# mk312_smt_main_V2a.net
KiCad netlist of a schematic drawn in EAGLE
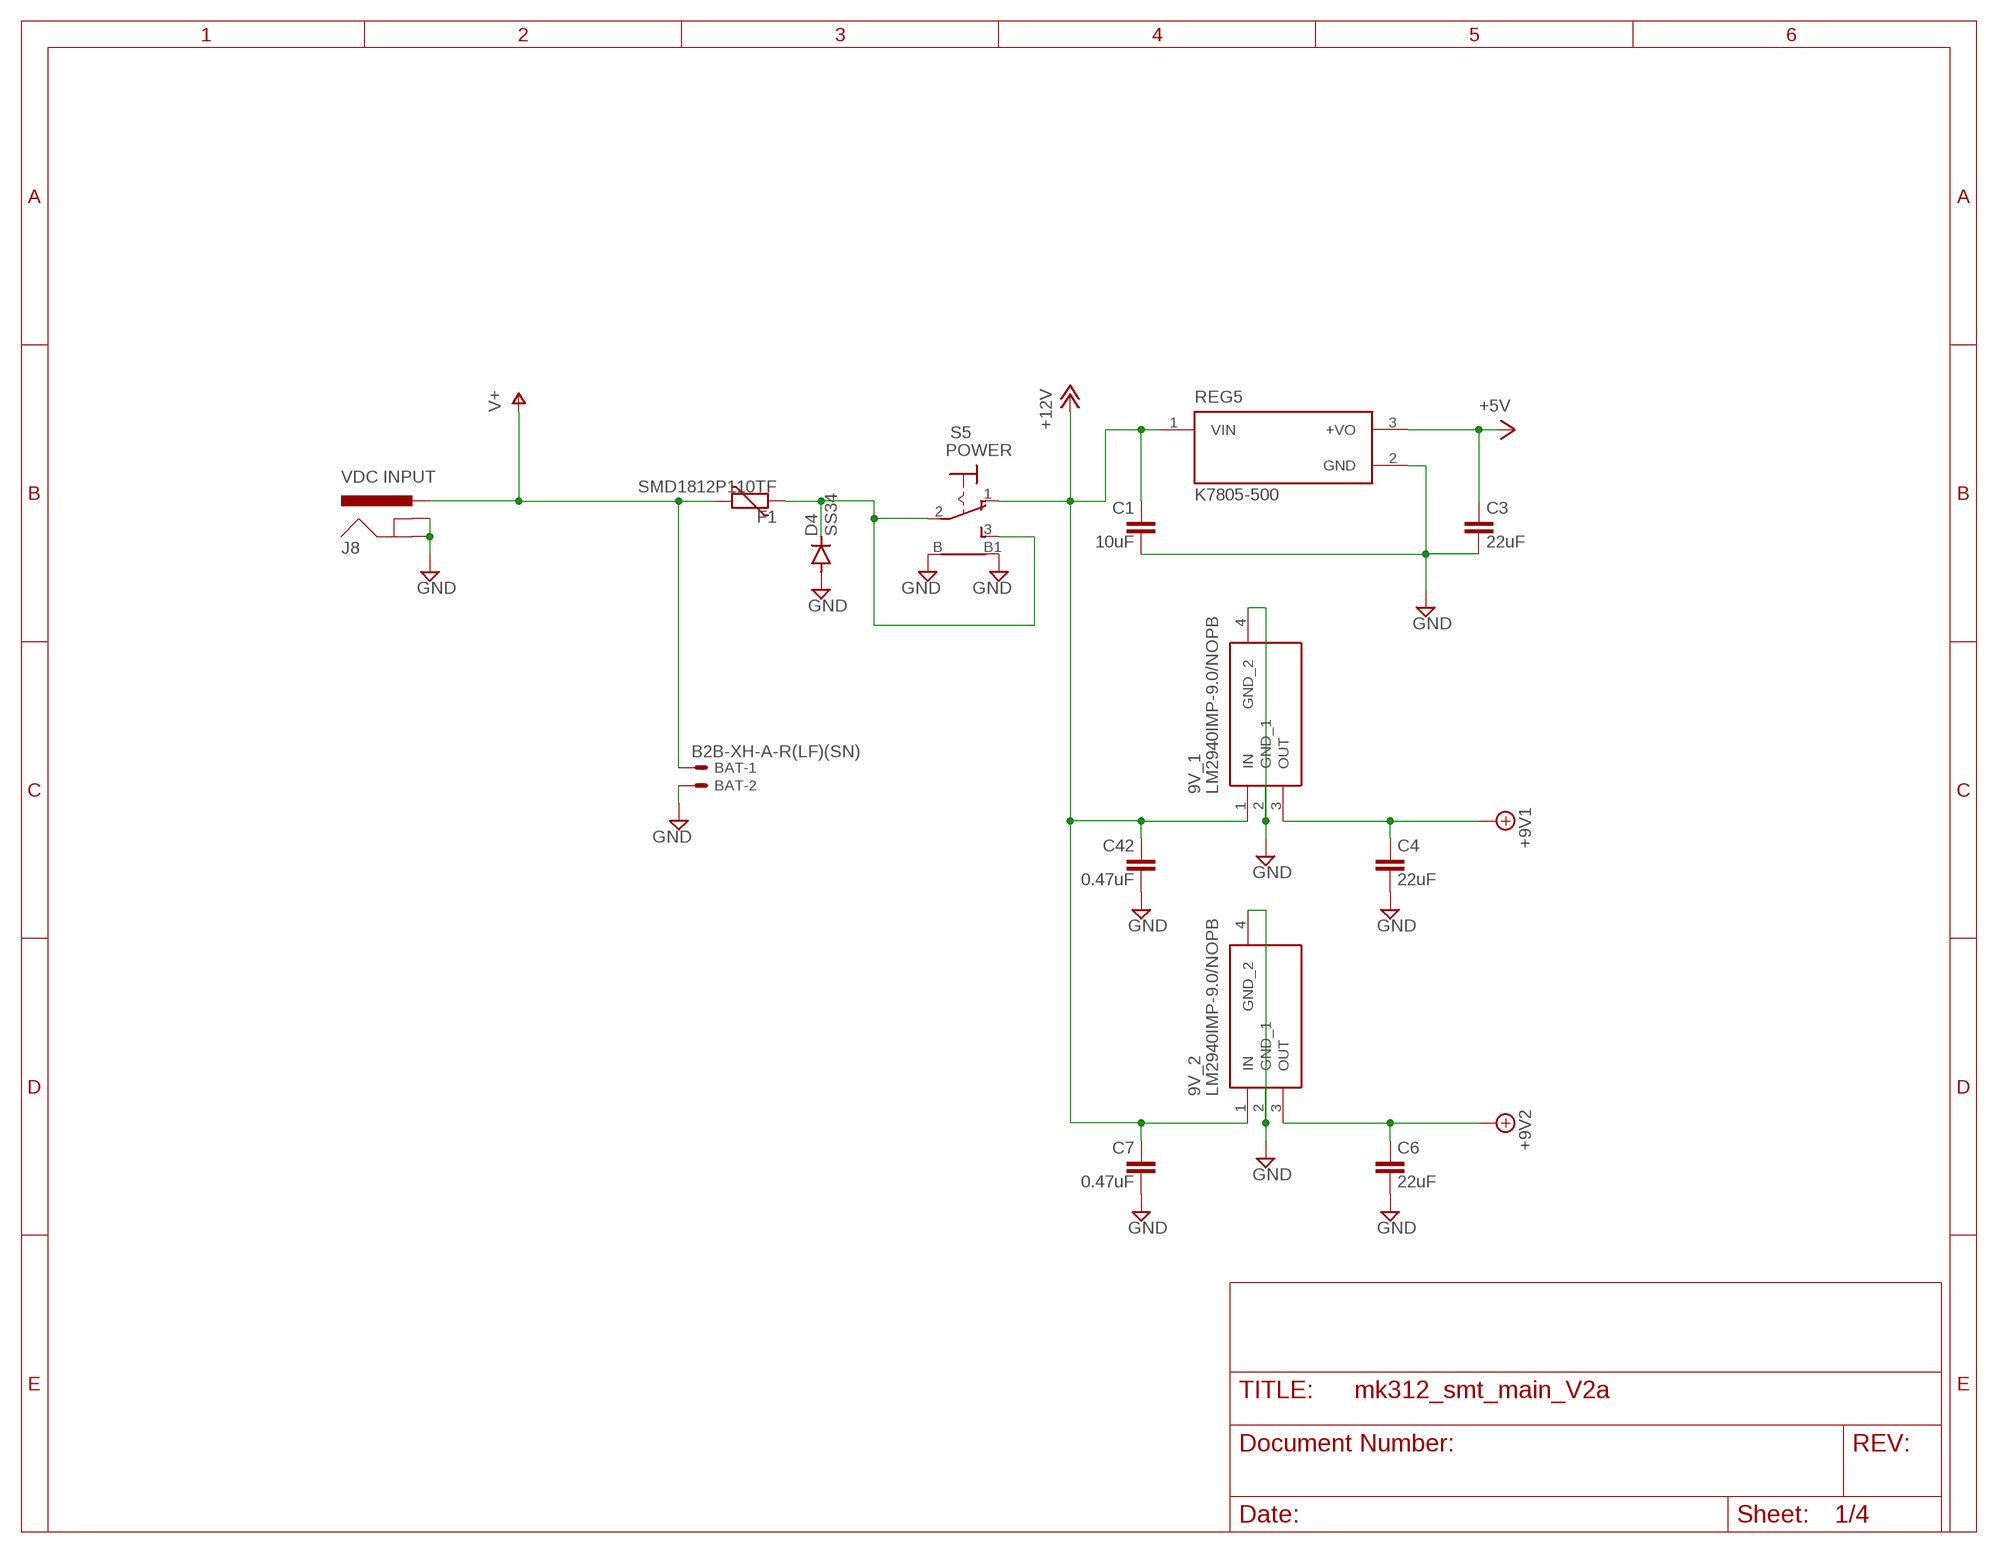
[diagram p0: schematic, sheet 1]
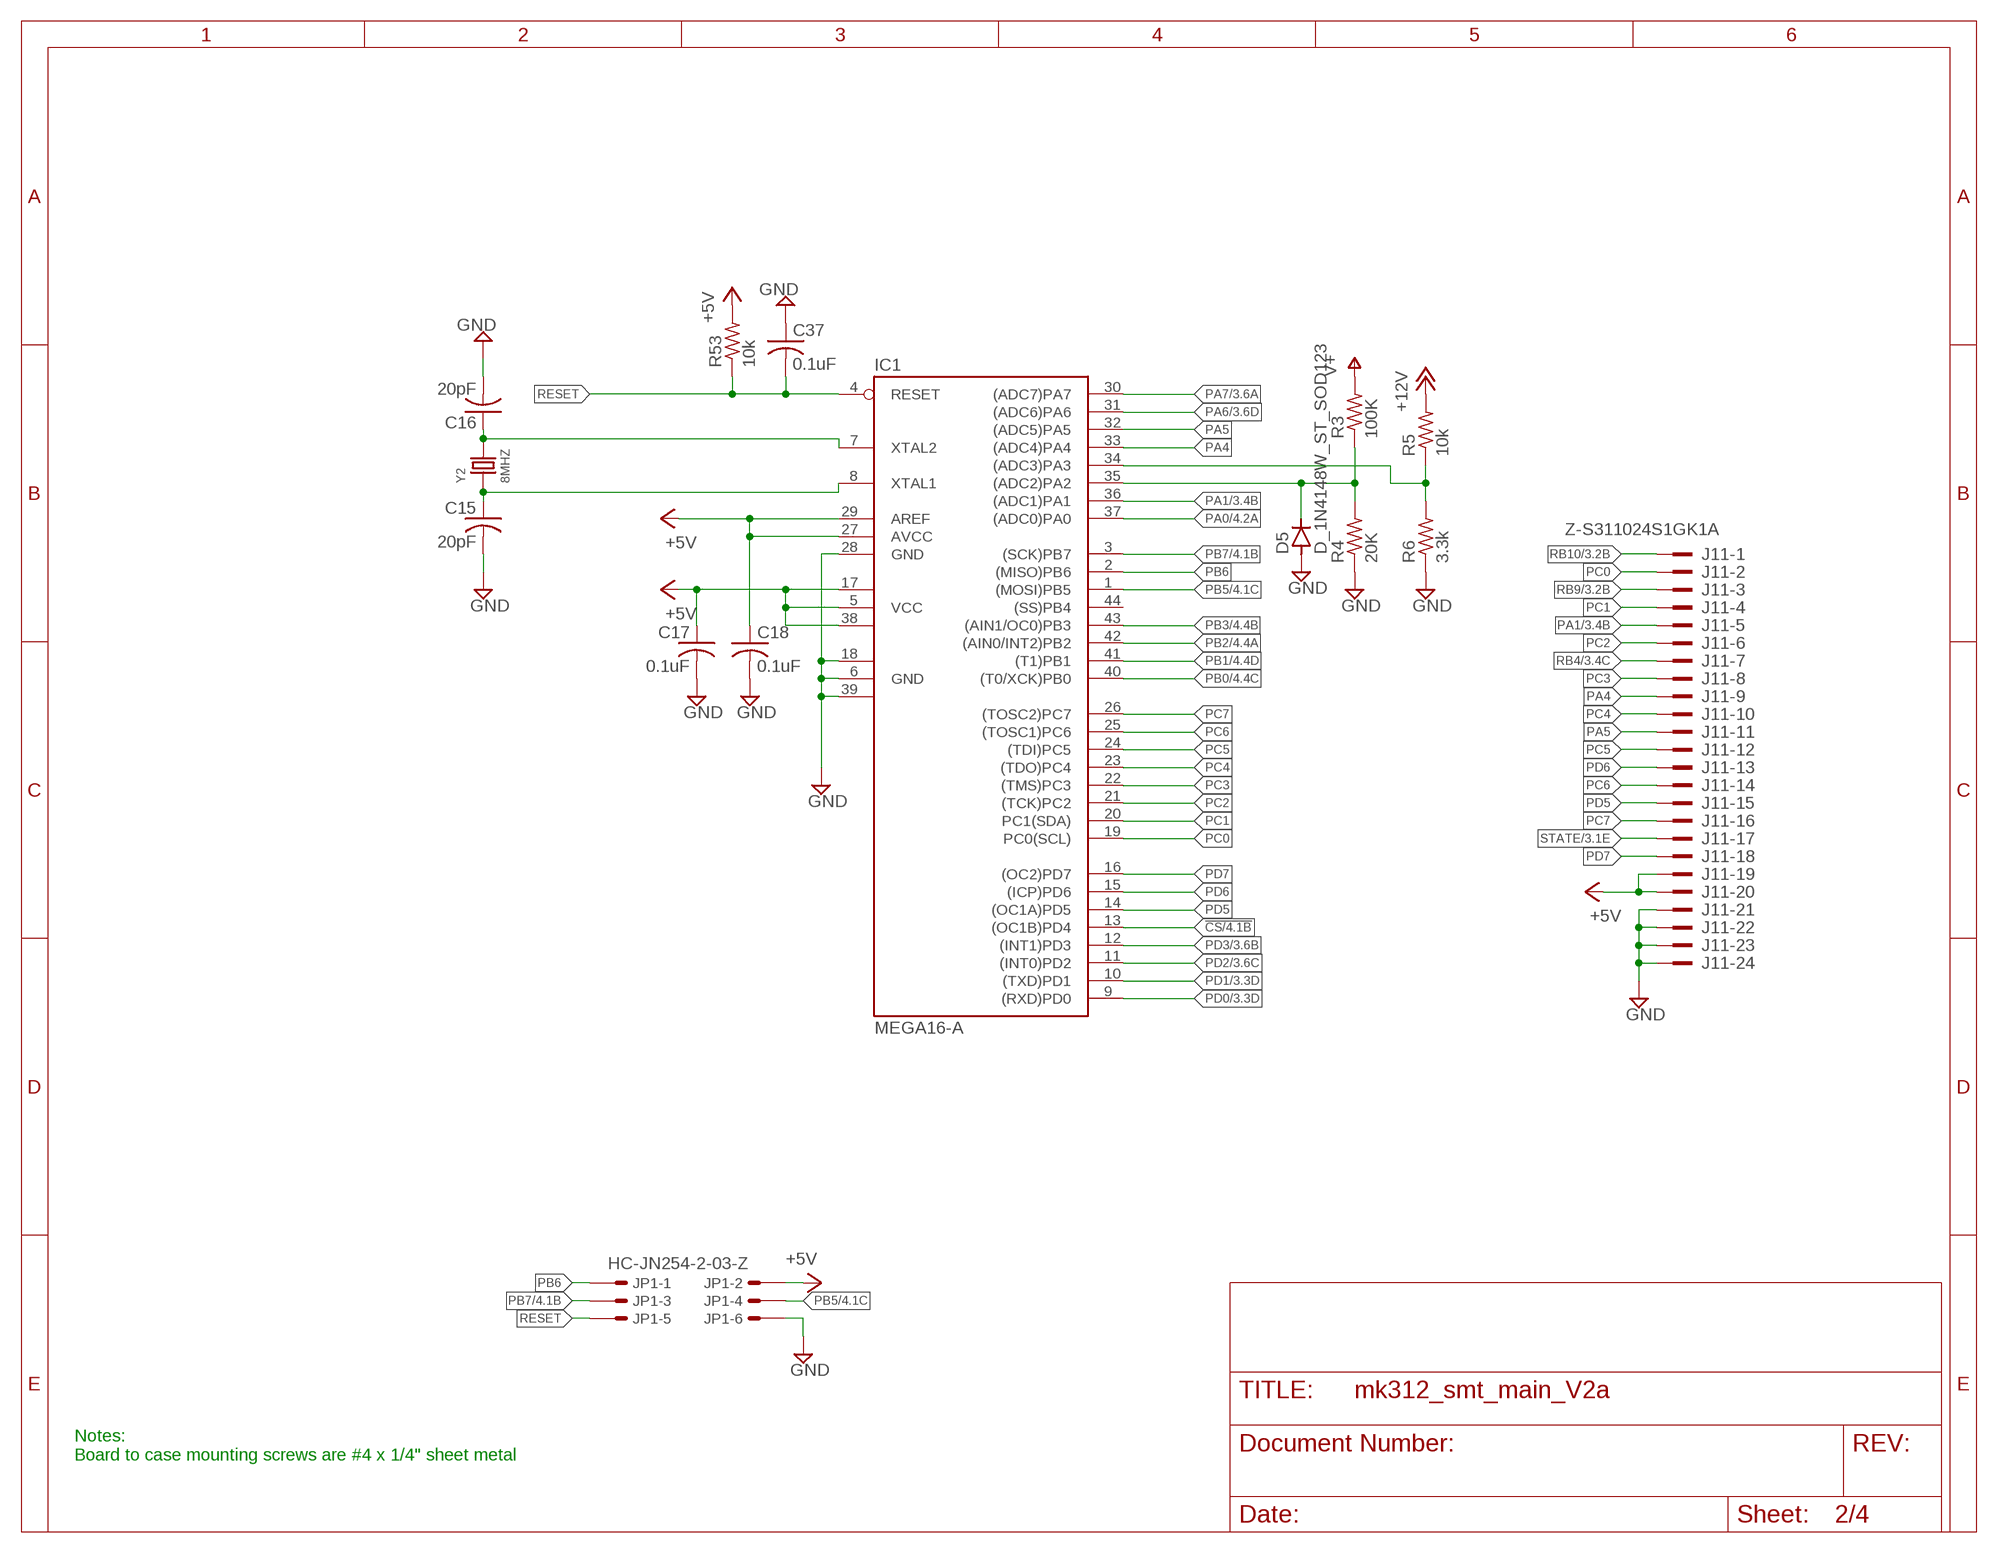
[diagram p1: schematic, sheet 2]
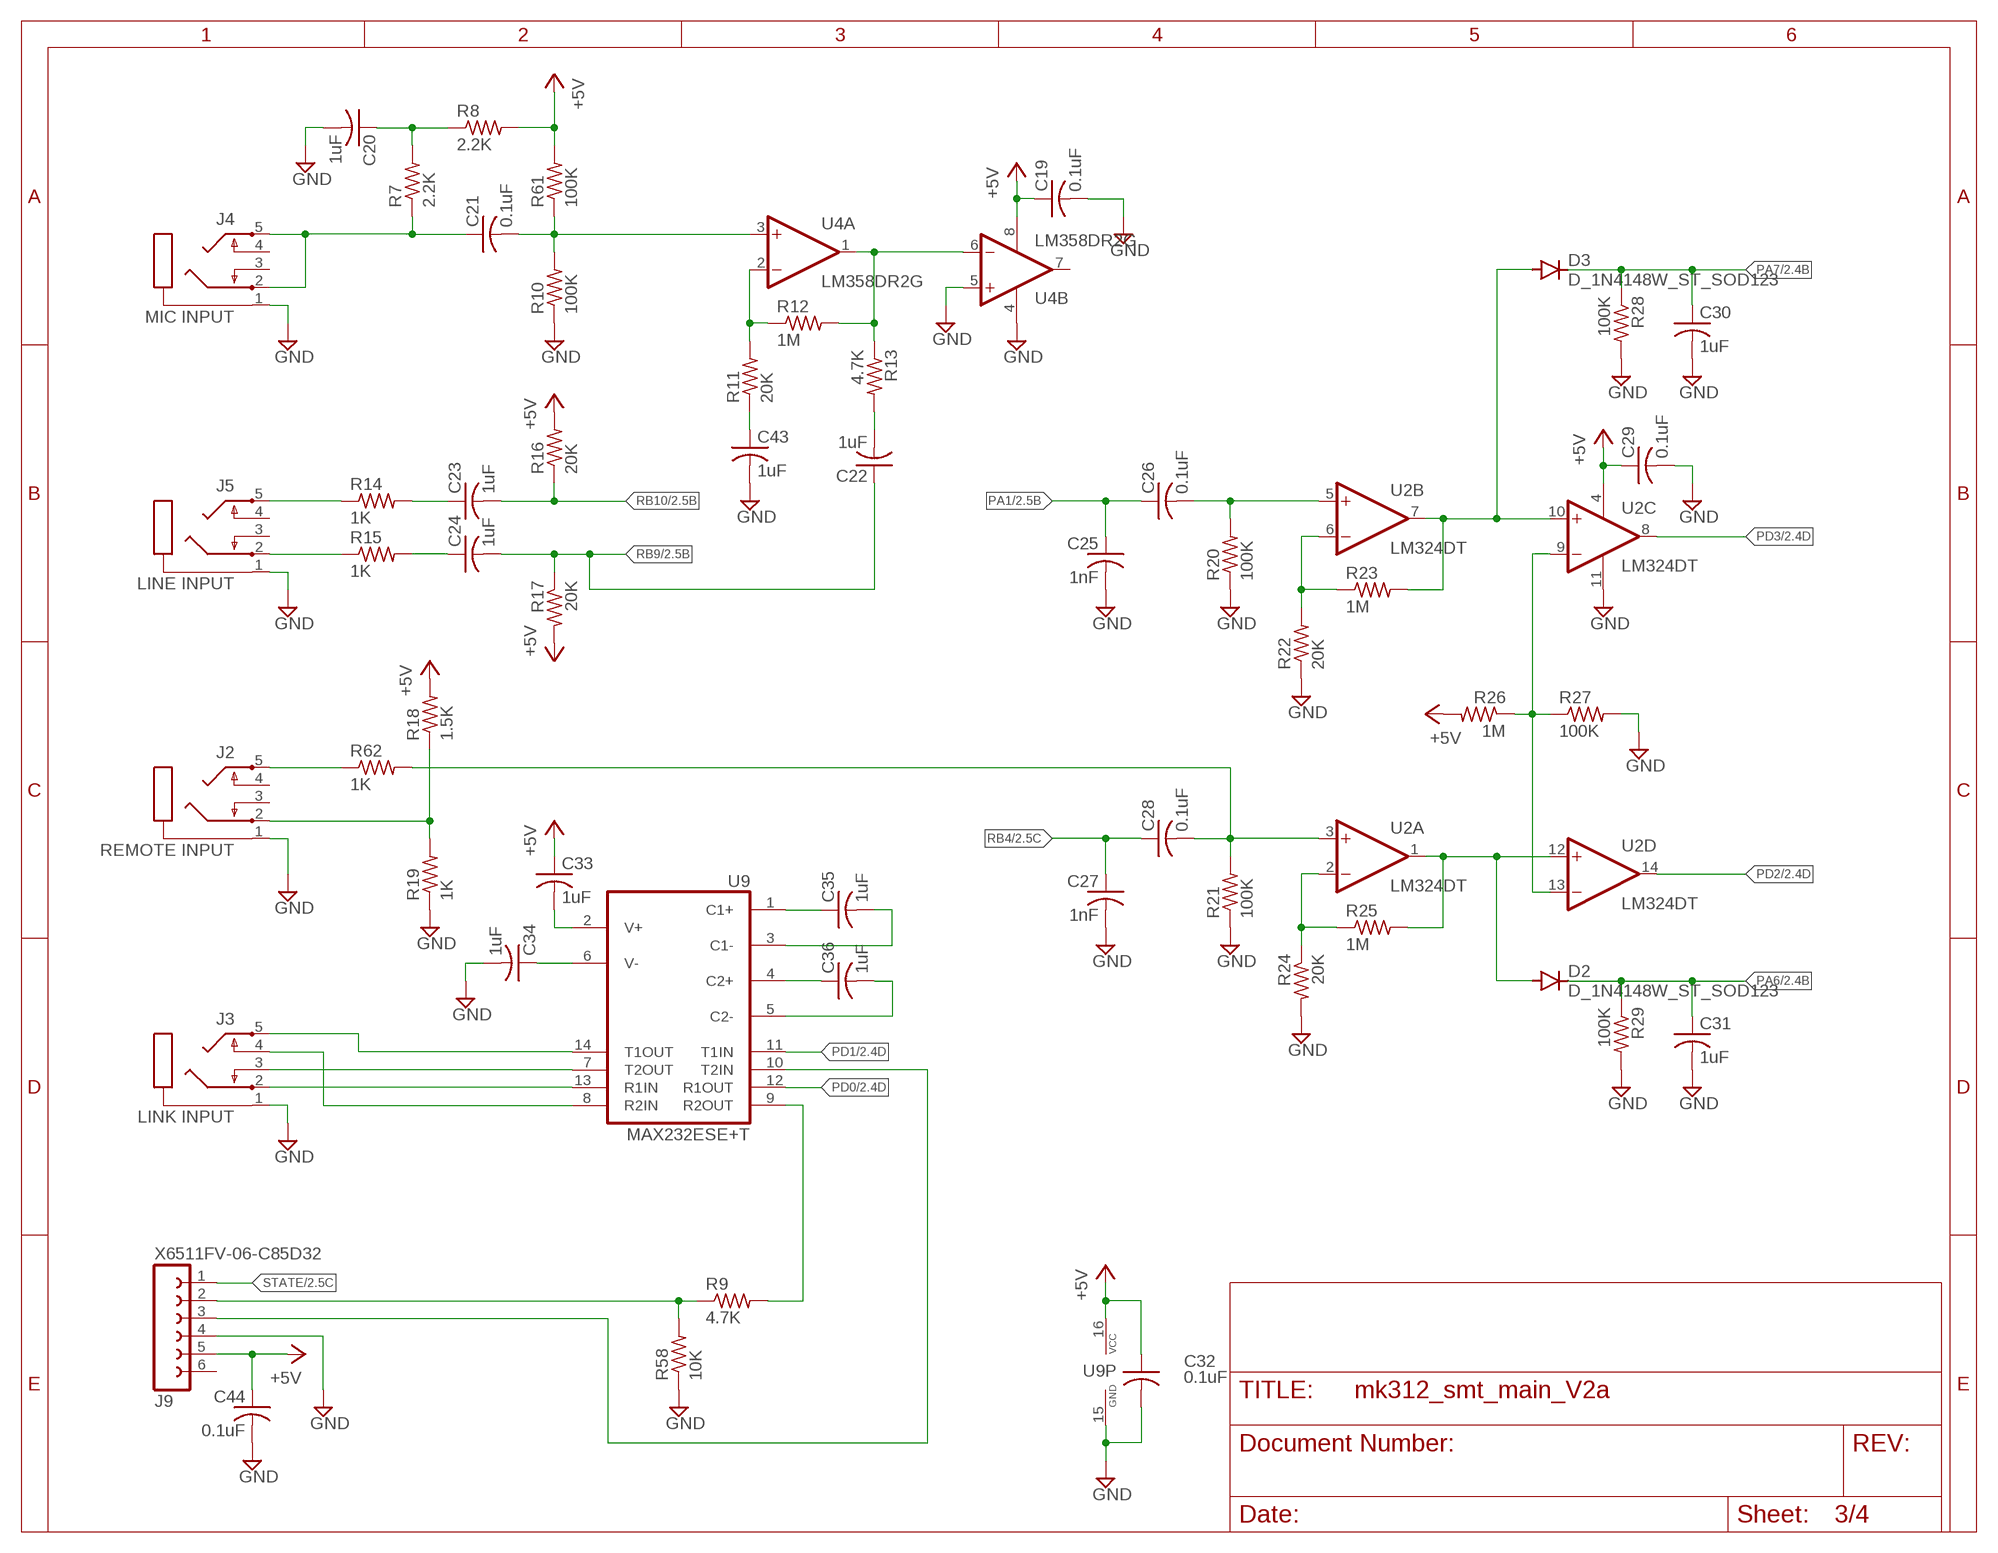
[diagram p2: schematic, sheet 3]
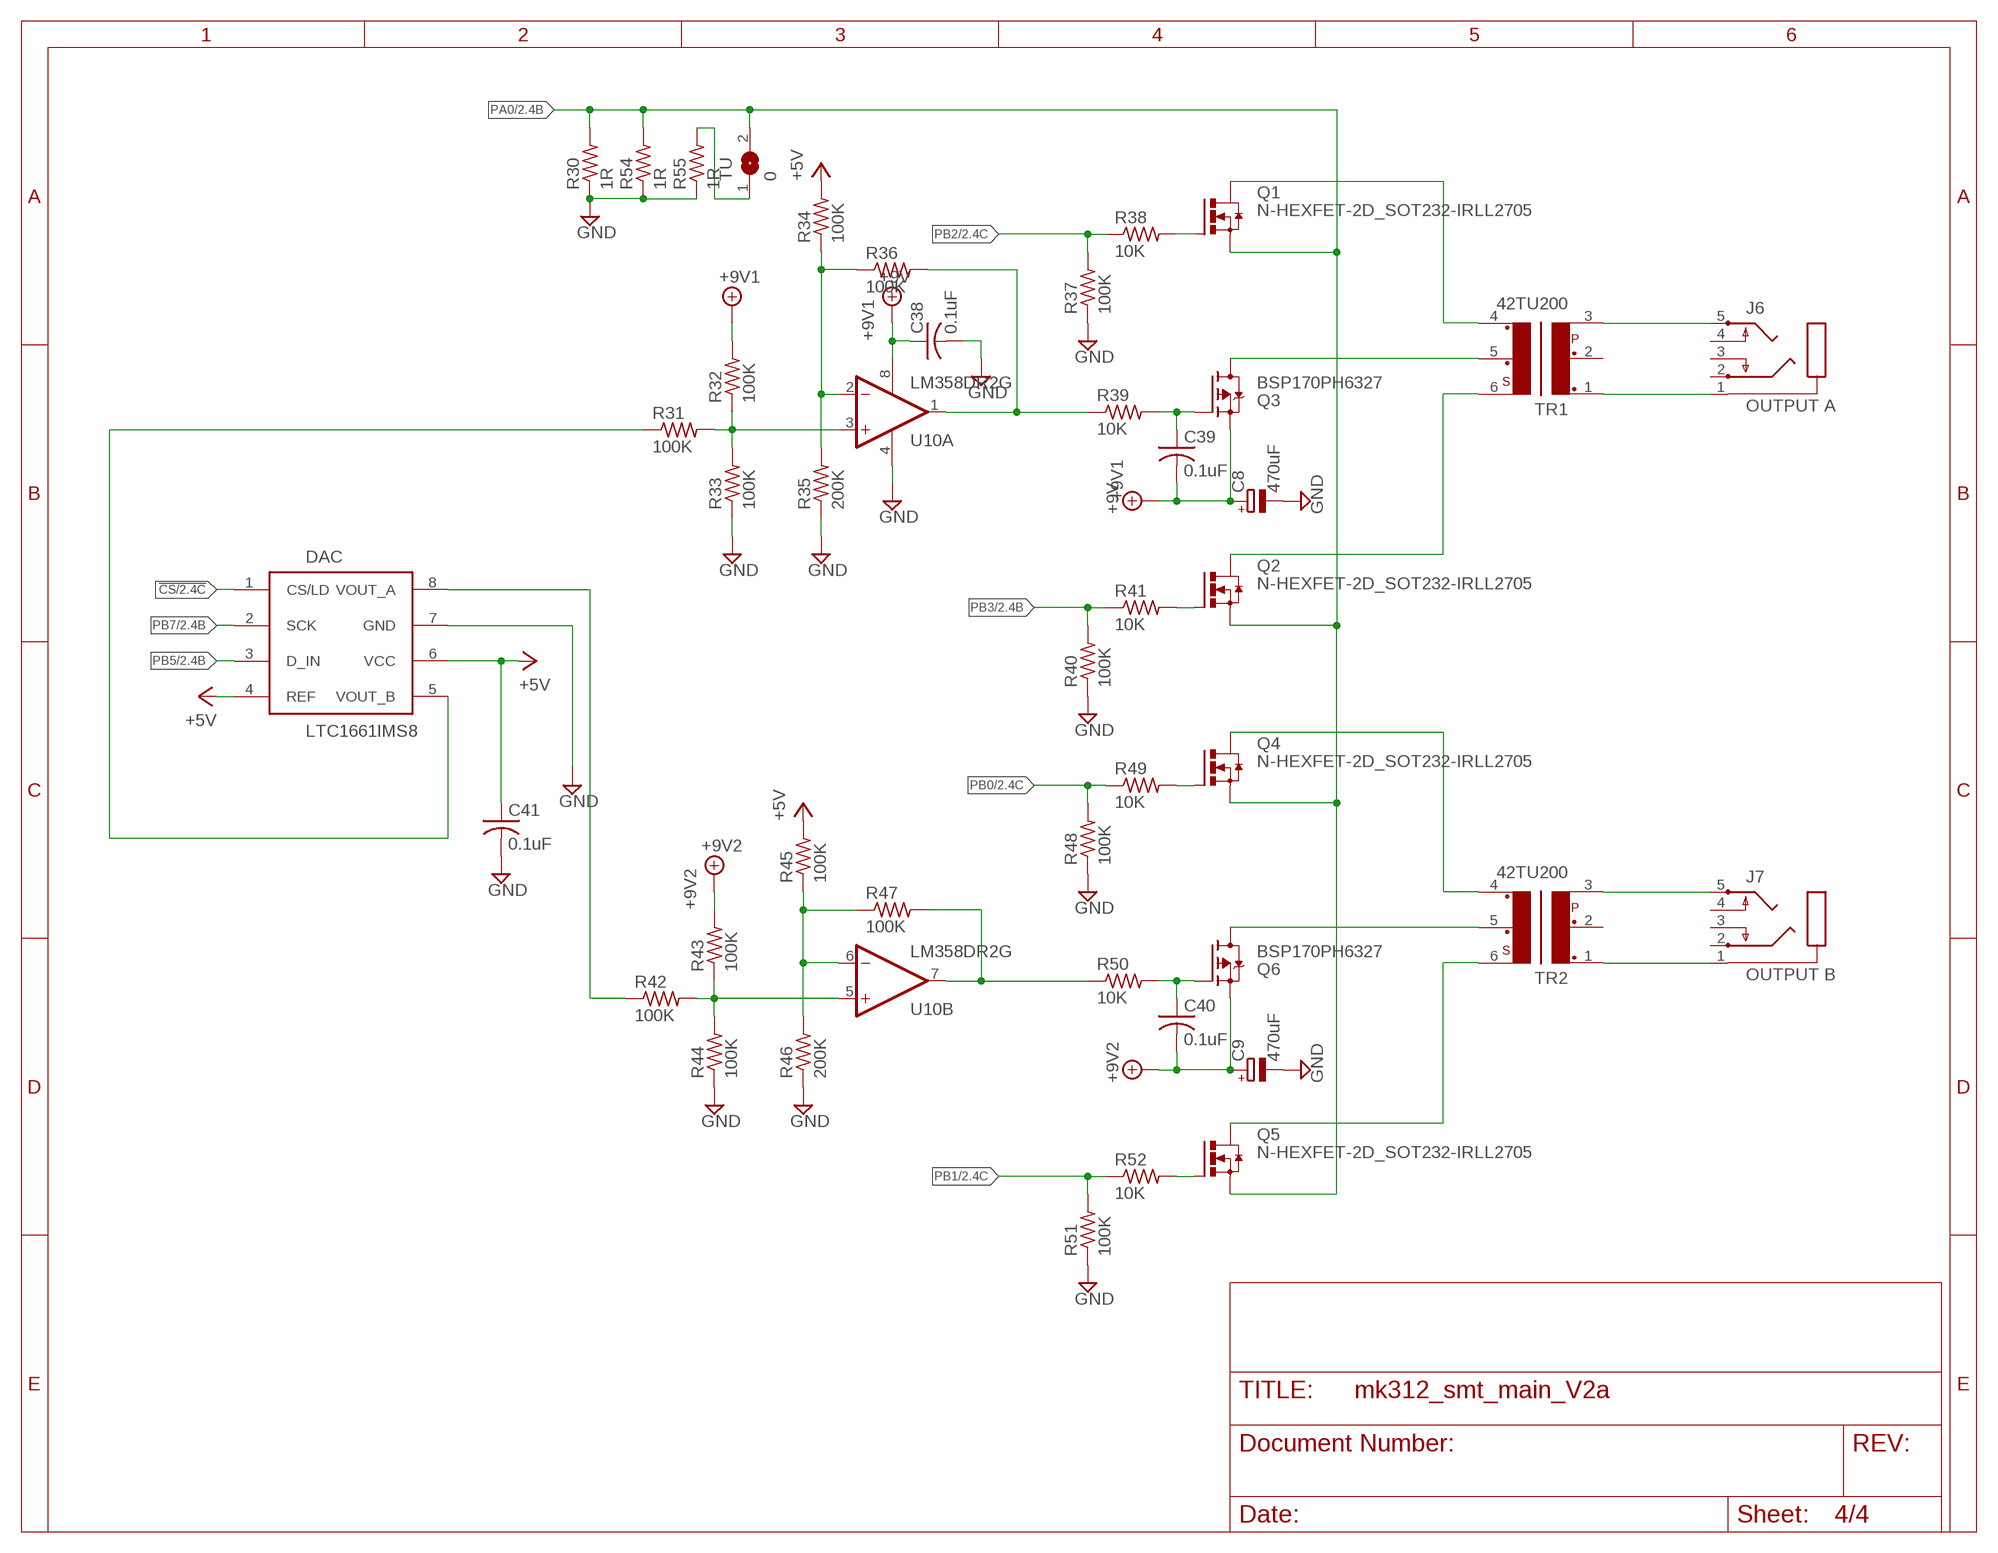
[diagram p3: schematic, sheet 4]

(export (version "E")
  (design (tool "Eeschema 10.0.6"))
  (components
    (comp (ref "C15")
      (value "20pF")
      (footprint "eagle-import:C0603")
      (libsource (lib "eagle-import") (part "C-USC0603"))
    )
    (comp (ref "C16")
      (value "20pF")
      (footprint "eagle-import:C0603")
      (libsource (lib "eagle-import") (part "C-USC0603"))
    )
    (comp (ref "C17")
      (value "0.1uF")
      (footprint "eagle-import:C0805")
      (libsource (lib "eagle-import") (part "C-USC0805"))
    )
    (comp (ref "C18")
      (value "0.1uF")
      (footprint "eagle-import:C0805")
      (libsource (lib "eagle-import") (part "C-USC0805"))
    )
    (comp (ref "C37")
      (value "0.1uF")
      (footprint "eagle-import:C0805")
      (libsource (lib "eagle-import") (part "rcl_334_C-USC0805"))
    )
    (comp (ref "D5")
      (value "D_1N4148W_ST_SOD123")
      (footprint "eagle-import:SOD123")
      (fields (field (name "LCSC_PART") "C81598"))
      (libsource (lib "eagle-import") (part "D__SOD1231N4148W_ST"))
    )
    (comp (ref "IC1")
      (value "MEGA16-A")
      (footprint "eagle-import:TQFP44")
      (fields (field (name "MPN") "ATMEGA16-16AU"))
      (libsource (lib "eagle-import") (part "MEGA16-A"))
    )
    (comp (ref "J11")
      (value "Z-S311024S1GK1A")
      (footprint "eagle-import:PAK100_2500-24")
      (libsource (lib "eagle-import") (part "2524-"))
    )
    (comp (ref "JP1")
      (value "HC-JN254-2-03-Z")
      (footprint "eagle-import:057-006-1")
      (libsource (lib "eagle-import") (part "057-006-1"))
    )
    (comp (ref "R3")
      (value "100K")
      (footprint "eagle-import:R0805")
      (libsource (lib "eagle-import") (part "R-US_R0805"))
    )
    (comp (ref "R4")
      (value "20K")
      (footprint "eagle-import:R0805")
      (libsource (lib "eagle-import") (part "R-US_R0805"))
    )
    (comp (ref "R5")
      (value "10k")
      (footprint "eagle-import:R0805")
      (libsource (lib "eagle-import") (part "R-US_R0805"))
    )
    (comp (ref "R6")
      (value "3.3k")
      (footprint "eagle-import:R0805")
      (libsource (lib "eagle-import") (part "R-US_R0805"))
    )
    (comp (ref "R53")
      (value "10k")
      (footprint "eagle-import:R0805")
      (libsource (lib "eagle-import") (part "rcl_334_R-US_R0805"))
    )
    (comp (ref "Y2")
      (value "8MHZ")
      (footprint "eagle-import:X2-SMD-5.0X3.2X1.3MM")
      (fields (field (name "MPN") "5032/2P"))
      (libsource (lib "eagle-import") (part "SMD-CRYSTAL-8MHZ-20PF-20PPM(2P-5.0X3.2MM)"))
    )
    (comp (ref "C8")
      (value "470uF")
      (footprint "eagle-import:150CLZ-1010")
      (libsource (lib "eagle-import") (part "CPOL-EU150CLZ-1010"))
    )
    (comp (ref "C9")
      (value "470uF")
      (footprint "eagle-import:150CLZ-1010")
      (libsource (lib "eagle-import") (part "CPOL-EU150CLZ-1010"))
    )
    (comp (ref "C38")
      (value "0.1uF")
      (footprint "eagle-import:C0805")
      (libsource (lib "eagle-import") (part "C-USC0805"))
    )
    (comp (ref "C39")
      (value "0.1uF")
      (footprint "eagle-import:C0805")
      (libsource (lib "eagle-import") (part "C-USC0805"))
    )
    (comp (ref "C40")
      (value "0.1uF")
      (footprint "eagle-import:C0805")
      (libsource (lib "eagle-import") (part "C-USC0805"))
    )
    (comp (ref "C41")
      (value "0.1uF")
      (footprint "eagle-import:C0805")
      (libsource (lib "eagle-import") (part "C-USC0805"))
    )
    (comp (ref "DAC")
      (value "LTC1661IMS8")
      (footprint "eagle-import:MSOP8")
      (libsource (lib "eagle-import") (part "LTC1661IMS8"))
    )
    (comp (ref "J6")
      (value "OUTPUT A")
      (footprint "eagle-import:PJ-3062")
      (libsource (lib "eagle-import") (part "STEREOJACKPJ-3062"))
    )
    (comp (ref "J7")
      (value "OUTPUT B")
      (footprint "eagle-import:PJ-3062")
      (libsource (lib "eagle-import") (part "STEREOJACKPJ-3062"))
    )
    (comp (ref "Q1")
      (value "N-HEXFET-2D_SOT232-IRLL2705")
      (footprint "eagle-import:SOT223")
      (libsource (lib "eagle-import") (part "N-HEXFET-2D_?-SOT232IRLL2705"))
    )
    (comp (ref "Q2")
      (value "N-HEXFET-2D_SOT232-IRLL2705")
      (footprint "eagle-import:SOT223")
      (libsource (lib "eagle-import") (part "N-HEXFET-2D_?-SOT232IRLL2705"))
    )
    (comp (ref "Q3")
      (value "BSP170PH6327")
      (footprint "eagle-import:SOT230P700X180-4N")
      (libsource (lib "eagle-import") (part "IRFL9014TRPBF"))
    )
    (comp (ref "Q4")
      (value "N-HEXFET-2D_SOT232-IRLL2705")
      (footprint "eagle-import:SOT223")
      (libsource (lib "eagle-import") (part "N-HEXFET-2D_?-SOT232IRLL2705"))
    )
    (comp (ref "Q5")
      (value "N-HEXFET-2D_SOT232-IRLL2705")
      (footprint "eagle-import:SOT223")
      (libsource (lib "eagle-import") (part "N-HEXFET-2D_?-SOT232IRLL2705"))
    )
    (comp (ref "Q6")
      (value "BSP170PH6327")
      (footprint "eagle-import:SOT230P700X180-4N")
      (libsource (lib "eagle-import") (part "IRFL9014TRPBF"))
    )
    (comp (ref "R30")
      (value "1R")
      (footprint "eagle-import:R1206")
      (libsource (lib "eagle-import") (part "R-US_R1206"))
    )
    (comp (ref "R31")
      (value "100K")
      (footprint "eagle-import:R0805")
      (libsource (lib "eagle-import") (part "R-US_R0805"))
    )
    (comp (ref "R32")
      (value "100K")
      (footprint "eagle-import:R0805")
      (libsource (lib "eagle-import") (part "R-US_R0805"))
    )
    (comp (ref "R33")
      (value "100K")
      (footprint "eagle-import:R0805")
      (libsource (lib "eagle-import") (part "R-US_R0805"))
    )
    (comp (ref "R34")
      (value "100K")
      (footprint "eagle-import:R0805")
      (libsource (lib "eagle-import") (part "R-US_R0805"))
    )
    (comp (ref "R35")
      (value "200K")
      (footprint "eagle-import:R0805")
      (libsource (lib "eagle-import") (part "R-US_R0805"))
    )
    (comp (ref "R36")
      (value "100K")
      (footprint "eagle-import:R0805")
      (libsource (lib "eagle-import") (part "R-US_R0805"))
    )
    (comp (ref "R37")
      (value "100K")
      (footprint "eagle-import:R0805")
      (libsource (lib "eagle-import") (part "R-US_R0805"))
    )
    (comp (ref "R38")
      (value "10K")
      (footprint "eagle-import:R0805")
      (libsource (lib "eagle-import") (part "R-US_R0805"))
    )
    (comp (ref "R39")
      (value "10K")
      (footprint "eagle-import:R0805")
      (libsource (lib "eagle-import") (part "R-US_R0805"))
    )
    (comp (ref "R40")
      (value "100K")
      (footprint "eagle-import:R0805")
      (libsource (lib "eagle-import") (part "R-US_R0805"))
    )
    (comp (ref "R41")
      (value "10K")
      (footprint "eagle-import:R0805")
      (libsource (lib "eagle-import") (part "R-US_R0805"))
    )
    (comp (ref "R42")
      (value "100K")
      (footprint "eagle-import:R0805")
      (libsource (lib "eagle-import") (part "R-US_R0805"))
    )
    (comp (ref "R43")
      (value "100K")
      (footprint "eagle-import:R0805")
      (libsource (lib "eagle-import") (part "R-US_R0805"))
    )
    (comp (ref "R44")
      (value "100K")
      (footprint "eagle-import:R0805")
      (libsource (lib "eagle-import") (part "R-US_R0805"))
    )
    (comp (ref "R45")
      (value "100K")
      (footprint "eagle-import:R0805")
      (libsource (lib "eagle-import") (part "R-US_R0805"))
    )
    (comp (ref "R46")
      (value "200K")
      (footprint "eagle-import:R0805")
      (libsource (lib "eagle-import") (part "R-US_R0805"))
    )
    (comp (ref "R47")
      (value "100K")
      (footprint "eagle-import:R0805")
      (libsource (lib "eagle-import") (part "R-US_R0805"))
    )
    (comp (ref "R48")
      (value "100K")
      (footprint "eagle-import:R0805")
      (libsource (lib "eagle-import") (part "R-US_R0805"))
    )
    (comp (ref "R49")
      (value "10K")
      (footprint "eagle-import:R0805")
      (libsource (lib "eagle-import") (part "R-US_R0805"))
    )
    (comp (ref "R50")
      (value "10K")
      (footprint "eagle-import:R0805")
      (libsource (lib "eagle-import") (part "R-US_R0805"))
    )
    (comp (ref "R51")
      (value "100K")
      (footprint "eagle-import:R0805")
      (libsource (lib "eagle-import") (part "R-US_R0805"))
    )
    (comp (ref "R52")
      (value "10K")
      (footprint "eagle-import:R0805")
      (libsource (lib "eagle-import") (part "R-US_R0805"))
    )
    (comp (ref "R54")
      (value "1R")
      (footprint "eagle-import:R1206")
      (libsource (lib "eagle-import") (part "R-US_R1206"))
    )
    (comp (ref "R55")
      (value "1R")
      (footprint "eagle-import:R1206")
      (libsource (lib "eagle-import") (part "R-US_R1206"))
    )
    (comp (ref "TR1")
      (value "42TU200")
      (footprint "eagle-import:42TL")
      (libsource (lib "eagle-import") (part "42T?42TU"))
    )
    (comp (ref "TR2")
      (value "42TU200")
      (footprint "eagle-import:42TL")
      (libsource (lib "eagle-import") (part "42T?42TU"))
    )
    (comp (ref "TU") (value "0") (footprint "eagle-import:SJ") (libsource (lib "eagle-import") (part "SJ")))
    (comp (ref "U10")
      (value "LM358DR2G")
      (footprint "eagle-import:SO08")
      (libsource (lib "eagle-import") (part "LM358D"))
    )
    (comp (ref "9V_1")
      (value "LM2940IMP-9.0/NOPB")
      (footprint "eagle-import:SOT230P700X180-4N")
      (fields (field (name "MOUSER_PART_NUMBER") "926-LM2940IMP90NOPB"))
      (libsource (lib "eagle-import") (part "LM2940IMP-9.0_NOPB"))
    )
    (comp (ref "9V_2")
      (value "LM2940IMP-9.0/NOPB")
      (footprint "eagle-import:SOT230P700X180-4N")
      (fields (field (name "MOUSER_PART_NUMBER") "926-LM2940IMP90NOPB"))
      (libsource (lib "eagle-import") (part "LM2940IMP-9.0_NOPB"))
    )
    (comp (ref "BAT")
      (value "B2B-XH-A-R(LF)(SN)")
      (footprint "eagle-import:JST-XH-02-PACKAGE-LONG-PAD")
      (libsource (lib "eagle-import") (part "JST-XH-02-PIN-LONG-PAD"))
    )
    (comp (ref "C1")
      (value "10uF")
      (footprint "eagle-import:C0805")
      (libsource (lib "eagle-import") (part "C-EUC0805"))
    )
    (comp (ref "C3")
      (value "22uF")
      (footprint "eagle-import:C1206")
      (libsource (lib "eagle-import") (part "C-EUC1206"))
    )
    (comp (ref "C4")
      (value "22uF")
      (footprint "eagle-import:C1206")
      (libsource (lib "eagle-import") (part "C-EUC1206"))
    )
    (comp (ref "C6")
      (value "22uF")
      (footprint "eagle-import:C1206")
      (libsource (lib "eagle-import") (part "C-EUC1206"))
    )
    (comp (ref "C7")
      (value "0.47uF")
      (footprint "eagle-import:C0805")
      (libsource (lib "eagle-import") (part "C-EUC0805"))
    )
    (comp (ref "C42")
      (value "0.47uF")
      (footprint "eagle-import:C0805")
      (libsource (lib "eagle-import") (part "C-EUC0805"))
    )
    (comp (ref "D4")
      (value "SS34")
      (footprint "eagle-import:SMA")
      (libsource (lib "eagle-import") (part "S1M"))
    )
    (comp (ref "F1")
      (value "SMD1812P110TF")
      (footprint "eagle-import:CT_CN1812")
      (libsource (lib "eagle-import") (part "VARISTORCN1812"))
    )
    (comp (ref "J8")
      (value "VDC INPUT")
      (footprint "eagle-import:POWER_JACK_PTH_SLOT")
      (libsource (lib "eagle-import") (part "POWER_JACKPOWER_JACK_SLOT"))
    )
    (comp (ref "REG5")
      (value "K7805-500")
      (footprint "eagle-import:CONV_K7809M-1000R3")
      (fields (field (name "MF") "Mornsun America, LLC") (field (name "MP") "K7809M-1000R3"))
      (libsource (lib "eagle-import") (part "K7809M-1000R3"))
    )
    (comp (ref "S5")
      (value "POWER")
      (footprint "eagle-import:LPV-1")
      (libsource (lib "eagle-import") (part "LPV-1"))
    )
    (comp (ref "C19")
      (value "0.1uF")
      (footprint "eagle-import:C0805")
      (libsource (lib "eagle-import") (part "C-USC0805"))
    )
    (comp (ref "C20")
      (value "1uF")
      (footprint "eagle-import:C0805")
      (libsource (lib "eagle-import") (part "C-USC0805"))
    )
    (comp (ref "C21")
      (value "0.1uF")
      (footprint "eagle-import:C0805")
      (libsource (lib "eagle-import") (part "C-USC0805"))
    )
    (comp (ref "C22")
      (value "1uF")
      (footprint "eagle-import:C0805")
      (libsource (lib "eagle-import") (part "C-USC0805"))
    )
    (comp (ref "C23")
      (value "1uF")
      (footprint "eagle-import:C0805")
      (libsource (lib "eagle-import") (part "C-USC0805"))
    )
    (comp (ref "C24")
      (value "1uF")
      (footprint "eagle-import:C0805")
      (libsource (lib "eagle-import") (part "C-USC0805"))
    )
    (comp (ref "C25")
      (value "1nF")
      (footprint "eagle-import:C0805")
      (libsource (lib "eagle-import") (part "C-USC0805"))
    )
    (comp (ref "C26")
      (value "0.1uF")
      (footprint "eagle-import:C0805")
      (libsource (lib "eagle-import") (part "C-USC0805"))
    )
    (comp (ref "C27")
      (value "1nF")
      (footprint "eagle-import:C0805")
      (libsource (lib "eagle-import") (part "C-USC0805"))
    )
    (comp (ref "C28")
      (value "0.1uF")
      (footprint "eagle-import:C0805")
      (libsource (lib "eagle-import") (part "C-USC0805"))
    )
    (comp (ref "C29")
      (value "0.1uF")
      (footprint "eagle-import:C0805")
      (libsource (lib "eagle-import") (part "C-USC0805"))
    )
    (comp (ref "C30")
      (value "1uF")
      (footprint "eagle-import:C0805")
      (libsource (lib "eagle-import") (part "C-USC0805"))
    )
    (comp (ref "C31")
      (value "1uF")
      (footprint "eagle-import:C0805")
      (libsource (lib "eagle-import") (part "C-USC0805"))
    )
    (comp (ref "C32")
      (value "0.1uF")
      (footprint "eagle-import:C0805")
      (libsource (lib "eagle-import") (part "C-USC0805"))
    )
    (comp (ref "C33")
      (value "1uF")
      (footprint "eagle-import:C0805")
      (libsource (lib "eagle-import") (part "C-USC0805"))
    )
    (comp (ref "C34")
      (value "1uF")
      (footprint "eagle-import:C0805")
      (libsource (lib "eagle-import") (part "C-USC0805"))
    )
    (comp (ref "C35")
      (value "1uF")
      (footprint "eagle-import:C0805")
      (libsource (lib "eagle-import") (part "C-USC0805"))
    )
    (comp (ref "C36")
      (value "1uF")
      (footprint "eagle-import:C0805")
      (libsource (lib "eagle-import") (part "C-USC0805"))
    )
    (comp (ref "C43")
      (value "1uF")
      (footprint "eagle-import:C0805")
      (libsource (lib "eagle-import") (part "C-USC0805"))
    )
    (comp (ref "C44")
      (value "0.1uF")
      (footprint "eagle-import:C0805")
      (libsource (lib "eagle-import") (part "C-USC0805"))
    )
    (comp (ref "D2")
      (value "D_1N4148W_ST_SOD123")
      (footprint "eagle-import:SOD123")
      (fields (field (name "LCSC_PART") "C81598"))
      (libsource (lib "eagle-import") (part "D__SOD1231N4148W_ST"))
    )
    (comp (ref "D3")
      (value "D_1N4148W_ST_SOD123")
      (footprint "eagle-import:SOD123")
      (fields (field (name "LCSC_PART") "C81598"))
      (libsource (lib "eagle-import") (part "D__SOD1231N4148W_ST"))
    )
    (comp (ref "J2")
      (value "REMOTE INPUT")
      (footprint "eagle-import:PJ-3062")
      (libsource (lib "eagle-import") (part "STEREOJACKPJ-3062"))
    )
    (comp (ref "J3")
      (value "LINK INPUT")
      (footprint "eagle-import:PJ-3062")
      (libsource (lib "eagle-import") (part "STEREOJACKPJ-3062"))
    )
    (comp (ref "J4")
      (value "MIC INPUT")
      (footprint "eagle-import:PJ-3062")
      (libsource (lib "eagle-import") (part "STEREOJACKPJ-3062"))
    )
    (comp (ref "J5")
      (value "LINE INPUT")
      (footprint "eagle-import:PJ-3062")
      (libsource (lib "eagle-import") (part "STEREOJACKPJ-3062"))
    )
    (comp (ref "J9")
      (value "X6511FV-06-C85D32")
      (footprint "eagle-import:FE06")
      (libsource (lib "eagle-import") (part "FE06-1"))
    )
    (comp (ref "R7")
      (value "2.2K")
      (footprint "eagle-import:R0805")
      (libsource (lib "eagle-import") (part "R-US_R0805"))
    )
    (comp (ref "R8")
      (value "2.2K")
      (footprint "eagle-import:R0805")
      (libsource (lib "eagle-import") (part "R-US_R0805"))
    )
    (comp (ref "R9")
      (value "4.7K")
      (footprint "eagle-import:R0805")
      (libsource (lib "eagle-import") (part "R-US_R0805"))
    )
    (comp (ref "R10")
      (value "100K")
      (footprint "eagle-import:R0805")
      (libsource (lib "eagle-import") (part "R-US_R0805"))
    )
    (comp (ref "R11")
      (value "20K")
      (footprint "eagle-import:R0805")
      (libsource (lib "eagle-import") (part "R-US_R0805"))
    )
    (comp (ref "R12")
      (value "1M")
      (footprint "eagle-import:R0805")
      (libsource (lib "eagle-import") (part "R-US_R0805"))
    )
    (comp (ref "R13")
      (value "4.7K")
      (footprint "eagle-import:R0805")
      (libsource (lib "eagle-import") (part "R-US_R0805"))
    )
    (comp (ref "R14")
      (value "1K")
      (footprint "eagle-import:R0805")
      (libsource (lib "eagle-import") (part "R-US_R0805"))
    )
    (comp (ref "R15")
      (value "1K")
      (footprint "eagle-import:R0805")
      (libsource (lib "eagle-import") (part "R-US_R0805"))
    )
    (comp (ref "R16")
      (value "20K")
      (footprint "eagle-import:R0805")
      (libsource (lib "eagle-import") (part "R-US_R0805"))
    )
    (comp (ref "R17")
      (value "20K")
      (footprint "eagle-import:R0805")
      (libsource (lib "eagle-import") (part "R-US_R0805"))
    )
    (comp (ref "R18")
      (value "1.5K")
      (footprint "eagle-import:R0805")
      (libsource (lib "eagle-import") (part "R-US_R0805"))
    )
    (comp (ref "R19")
      (value "1K")
      (footprint "eagle-import:R0805")
      (libsource (lib "eagle-import") (part "R-US_R0805"))
    )
    (comp (ref "R20")
      (value "100K")
      (footprint "eagle-import:R0805")
      (libsource (lib "eagle-import") (part "R-US_R0805"))
    )
    (comp (ref "R21")
      (value "100K")
      (footprint "eagle-import:R0805")
      (libsource (lib "eagle-import") (part "R-US_R0805"))
    )
    (comp (ref "R22")
      (value "20K")
      (footprint "eagle-import:R0805")
      (libsource (lib "eagle-import") (part "R-US_R0805"))
    )
    (comp (ref "R23")
      (value "1M")
      (footprint "eagle-import:R0805")
      (libsource (lib "eagle-import") (part "R-US_R0805"))
    )
    (comp (ref "R24")
      (value "20K")
      (footprint "eagle-import:R0805")
      (libsource (lib "eagle-import") (part "R-US_R0805"))
    )
    (comp (ref "R25")
      (value "1M")
      (footprint "eagle-import:R0805")
      (libsource (lib "eagle-import") (part "R-US_R0805"))
    )
    (comp (ref "R26")
      (value "1M")
      (footprint "eagle-import:R0805")
      (libsource (lib "eagle-import") (part "R-US_R0805"))
    )
    (comp (ref "R27")
      (value "100K")
      (footprint "eagle-import:R0805")
      (libsource (lib "eagle-import") (part "R-US_R0805"))
    )
    (comp (ref "R28")
      (value "100K")
      (footprint "eagle-import:R0805")
      (libsource (lib "eagle-import") (part "R-US_R0805"))
    )
    (comp (ref "R29")
      (value "100K")
      (footprint "eagle-import:R0805")
      (libsource (lib "eagle-import") (part "R-US_R0805"))
    )
    (comp (ref "R58")
      (value "10K")
      (footprint "eagle-import:R0805")
      (libsource (lib "eagle-import") (part "R-US_R0805"))
    )
    (comp (ref "R61")
      (value "100K")
      (footprint "eagle-import:R0805")
      (libsource (lib "eagle-import") (part "R-US_R0805"))
    )
    (comp (ref "R62")
      (value "1K")
      (footprint "eagle-import:R0805")
      (libsource (lib "eagle-import") (part "R-US_R0805"))
    )
    (comp (ref "U2")
      (value "LM324DT")
      (footprint "eagle-import:SO14")
      (libsource (lib "eagle-import") (part "LM324D"))
    )
    (comp (ref "U4")
      (value "LM358DR2G")
      (footprint "eagle-import:SO08")
      (libsource (lib "eagle-import") (part "LM358D"))
    )
    (comp (ref "U9")
      (value "MAX232ESE+T")
      (footprint "eagle-import:SOP-16")
      (libsource (lib "eagle-import") (part "MAX232ECWESOP16"))
    )
  )
  (nets
    (net (code "1") (name "+5V") (class "Default")
      (node (ref "C17") (pin "1") (pinfunction "1_1") (pintype "passive"))
      (node (ref "C18") (pin "1") (pinfunction "1_1") (pintype "passive"))
      (node (ref "C19") (pin "1") (pinfunction "1_1") (pintype "passive"))
      (node (ref "C29") (pin "1") (pinfunction "1_1") (pintype "passive"))
      (node (ref "C3") (pin "1") (pinfunction "1_1") (pintype "passive"))
      (node (ref "C32") (pin "1") (pinfunction "1_1") (pintype "passive"))
      (node (ref "C33") (pin "1") (pinfunction "1_1") (pintype "passive"))
      (node (ref "C41") (pin "1") (pinfunction "1_1") (pintype "passive"))
      (node (ref "C44") (pin "1") (pinfunction "1_1") (pintype "passive"))
      (node (ref "DAC") (pin "4") (pinfunction "REF_4") (pintype "input"))
      (node (ref "DAC") (pin "6") (pinfunction "VCC_6") (pintype "power_in"))
      (node (ref "IC1") (pin "17") (pinfunction "VCC1_17") (pintype "power_in"))
      (node (ref "IC1") (pin "27") (pinfunction "AVCC_27") (pintype "power_in"))
      (node (ref "IC1") (pin "29") (pinfunction "AREF_29") (pintype "passive"))
      (node (ref "IC1") (pin "38") (pinfunction "VCC2_38") (pintype "power_in"))
      (node (ref "IC1") (pin "5") (pinfunction "VCC_5") (pintype "power_in"))
      (node (ref "J11") (pin "19") (pinfunction "KL_19") (pintype "passive"))
      (node (ref "J11") (pin "20") (pinfunction "KL_20") (pintype "passive"))
      (node (ref "J9") (pin "5") (pinfunction "5_5") (pintype "passive"))
      (node (ref "JP1") (pin "2") (pinfunction "S_2") (pintype "passive"))
      (node (ref "R16") (pin "2") (pinfunction "2_2") (pintype "passive"))
      (node (ref "R17") (pin "2") (pinfunction "2_2") (pintype "passive"))
      (node (ref "R18") (pin "2") (pinfunction "2_2") (pintype "passive"))
      (node (ref "R26") (pin "2") (pinfunction "2_2") (pintype "passive"))
      (node (ref "R34") (pin "2") (pinfunction "2_2") (pintype "passive"))
      (node (ref "R45") (pin "2") (pinfunction "2_2") (pintype "passive"))
      (node (ref "R53") (pin "2") (pinfunction "2_2") (pintype "passive"))
      (node (ref "R61") (pin "2") (pinfunction "2_2") (pintype "passive"))
      (node (ref "R8") (pin "2") (pinfunction "2_2") (pintype "passive"))
      (node (ref "REG5") (pin "3") (pinfunction "+VO_3") (pintype "output"))
      (node (ref "U2") (pin "4") (pinfunction "V+_4") (pintype "power_in"))
      (node (ref "U4") (pin "8") (pinfunction "V+_8") (pintype "power_in"))
      (node (ref "U9") (pin "16") (pinfunction "VCC_16") (pintype "power_in"))
    )
    (net (code "2") (name "+9V1") (class "Default")
      (node (ref "9V_1") (pin "3") (pinfunction "OUT_3") (pintype "power_in"))
      (node (ref "C38") (pin "1") (pinfunction "1_1") (pintype "passive"))
      (node (ref "C39") (pin "2") (pinfunction "2_2") (pintype "passive"))
      (node (ref "C4") (pin "1") (pinfunction "1_1") (pintype "passive"))
      (node (ref "C8") (pin "+") (pinfunction "+_+") (pintype "passive"))
      (node (ref "Q3") (pin "3") (pinfunction "S_3") (pintype "passive"))
      (node (ref "R32") (pin "2") (pinfunction "2_2") (pintype "passive"))
      (node (ref "U10") (pin "8") (pinfunction "V+_8") (pintype "power_in"))
    )
    (net (code "3") (name "+9V2") (class "Default")
      (node (ref "9V_2") (pin "3") (pinfunction "OUT_3") (pintype "power_in"))
      (node (ref "C40") (pin "2") (pinfunction "2_2") (pintype "passive"))
      (node (ref "C6") (pin "1") (pinfunction "1_1") (pintype "passive"))
      (node (ref "C9") (pin "+") (pinfunction "+_+") (pintype "passive"))
      (node (ref "Q6") (pin "3") (pinfunction "S_3") (pintype "passive"))
      (node (ref "R43") (pin "2") (pinfunction "2_2") (pintype "passive"))
    )
    (net (code "4") (name "+12V") (class "Default")
      (node (ref "9V_1") (pin "1") (pinfunction "IN_1") (pintype "input"))
      (node (ref "9V_2") (pin "1") (pinfunction "IN_1") (pintype "input"))
      (node (ref "C1") (pin "1") (pinfunction "1_1") (pintype "passive"))
      (node (ref "C42") (pin "1") (pinfunction "1_1") (pintype "passive"))
      (node (ref "C7") (pin "1") (pinfunction "1_1") (pintype "passive"))
      (node (ref "R5") (pin "2") (pinfunction "2_2") (pintype "passive"))
      (node (ref "REG5") (pin "1") (pinfunction "VIN_1") (pintype "input"))
      (node (ref "S5") (pin "1") (pinfunction "O_1") (pintype "passive"))
    )
    (net (code "5") (name "GND") (class "Default")
      (node (ref "9V_1") (pin "2") (pinfunction "GND_1_2") (pintype "power_in"))
      (node (ref "9V_1") (pin "4") (pinfunction "GND_2_4") (pintype "power_in"))
      (node (ref "9V_2") (pin "2") (pinfunction "GND_1_2") (pintype "power_in"))
      (node (ref "9V_2") (pin "4") (pinfunction "GND_2_4") (pintype "power_in"))
      (node (ref "BAT") (pin "2") (pinfunction "S_2") (pintype "passive"))
      (node (ref "C1") (pin "2") (pinfunction "2_2") (pintype "passive"))
      (node (ref "C15") (pin "2") (pinfunction "2_2") (pintype "passive"))
      (node (ref "C16") (pin "2") (pinfunction "2_2") (pintype "passive"))
      (node (ref "C17") (pin "2") (pinfunction "2_2") (pintype "passive"))
      (node (ref "C18") (pin "2") (pinfunction "2_2") (pintype "passive"))
      (node (ref "C19") (pin "2") (pinfunction "2_2") (pintype "passive"))
      (node (ref "C20") (pin "2") (pinfunction "2_2") (pintype "passive"))
      (node (ref "C25") (pin "2") (pinfunction "2_2") (pintype "passive"))
      (node (ref "C27") (pin "2") (pinfunction "2_2") (pintype "passive"))
      (node (ref "C29") (pin "2") (pinfunction "2_2") (pintype "passive"))
      (node (ref "C3") (pin "2") (pinfunction "2_2") (pintype "passive"))
      (node (ref "C30") (pin "2") (pinfunction "2_2") (pintype "passive"))
      (node (ref "C31") (pin "2") (pinfunction "2_2") (pintype "passive"))
      (node (ref "C32") (pin "2") (pinfunction "2_2") (pintype "passive"))
      (node (ref "C34") (pin "2") (pinfunction "2_2") (pintype "passive"))
      (node (ref "C37") (pin "1") (pinfunction "1_1") (pintype "passive"))
      (node (ref "C38") (pin "2") (pinfunction "2_2") (pintype "passive"))
      (node (ref "C4") (pin "2") (pinfunction "2_2") (pintype "passive"))
      (node (ref "C41") (pin "2") (pinfunction "2_2") (pintype "passive"))
      (node (ref "C42") (pin "2") (pinfunction "2_2") (pintype "passive"))
      (node (ref "C43") (pin "2") (pinfunction "2_2") (pintype "passive"))
      (node (ref "C44") (pin "2") (pinfunction "2_2") (pintype "passive"))
      (node (ref "C6") (pin "2") (pinfunction "2_2") (pintype "passive"))
      (node (ref "C7") (pin "2") (pinfunction "2_2") (pintype "passive"))
      (node (ref "C8") (pin "-") (pinfunction "-_-") (pintype "passive"))
      (node (ref "C9") (pin "-") (pinfunction "-_-") (pintype "passive"))
      (node (ref "D4") (pin "A") (pinfunction "A_A") (pintype "passive"))
      (node (ref "D5") (pin "A") (pinfunction "A_A") (pintype "passive"))
      (node (ref "DAC") (pin "7") (pinfunction "GND_7") (pintype "power_in"))
      (node (ref "IC1") (pin "18") (pinfunction "GND1_18") (pintype "power_in"))
      (node (ref "IC1") (pin "28") (pinfunction "GND_28") (pintype "power_in"))
      (node (ref "IC1") (pin "39") (pinfunction "GND2_39") (pintype "power_in"))
      (node (ref "IC1") (pin "6") (pinfunction "GND_6") (pintype "power_in"))
      (node (ref "J11") (pin "21") (pinfunction "KL_21") (pintype "passive"))
      (node (ref "J11") (pin "22") (pinfunction "KL_22") (pintype "passive"))
      (node (ref "J11") (pin "23") (pinfunction "KL_23") (pintype "passive"))
      (node (ref "J11") (pin "24") (pinfunction "KL_24") (pintype "passive"))
      (node (ref "J2") (pin "1") (pinfunction "1_1") (pintype "passive"))
      (node (ref "J3") (pin "1") (pinfunction "1_1") (pintype "passive"))
      (node (ref "J4") (pin "1") (pinfunction "1_1") (pintype "passive"))
      (node (ref "J5") (pin "1") (pinfunction "1_1") (pintype "passive"))
      (node (ref "J8") (pin "GND") (pinfunction "GND_GND") (pintype "bidirectional"))
      (node (ref "J8") (pin "GNDBREAK") (pinfunction "GNDBREAK_GNDBREAK") (pintype "bidirectional"))
      (node (ref "J9") (pin "4") (pinfunction "4_4") (pintype "passive"))
      (node (ref "JP1") (pin "6") (pinfunction "S_6") (pintype "passive"))
      (node (ref "R10") (pin "1") (pinfunction "1_1") (pintype "passive"))
      (node (ref "R19") (pin "1") (pinfunction "1_1") (pintype "passive"))
      (node (ref "R20") (pin "1") (pinfunction "1_1") (pintype "passive"))
      (node (ref "R21") (pin "1") (pinfunction "1_1") (pintype "passive"))
      (node (ref "R22") (pin "1") (pinfunction "1_1") (pintype "passive"))
      (node (ref "R24") (pin "2") (pinfunction "2_2") (pintype "passive"))
      (node (ref "R27") (pin "2") (pinfunction "2_2") (pintype "passive"))
      (node (ref "R28") (pin "2") (pinfunction "2_2") (pintype "passive"))
      (node (ref "R29") (pin "2") (pinfunction "2_2") (pintype "passive"))
      (node (ref "R30") (pin "1") (pinfunction "1_1") (pintype "passive"))
      (node (ref "R33") (pin "1") (pinfunction "1_1") (pintype "passive"))
      (node (ref "R35") (pin "1") (pinfunction "1_1") (pintype "passive"))
      (node (ref "R37") (pin "1") (pinfunction "1_1") (pintype "passive"))
      (node (ref "R4") (pin "1") (pinfunction "1_1") (pintype "passive"))
      (node (ref "R40") (pin "1") (pinfunction "1_1") (pintype "passive"))
      (node (ref "R44") (pin "1") (pinfunction "1_1") (pintype "passive"))
      (node (ref "R46") (pin "1") (pinfunction "1_1") (pintype "passive"))
      (node (ref "R48") (pin "1") (pinfunction "1_1") (pintype "passive"))
      (node (ref "R51") (pin "1") (pinfunction "1_1") (pintype "passive"))
      (node (ref "R54") (pin "1") (pinfunction "1_1") (pintype "passive"))
      (node (ref "R55") (pin "1") (pinfunction "1_1") (pintype "passive"))
      (node (ref "R58") (pin "1") (pinfunction "1_1") (pintype "passive"))
      (node (ref "R6") (pin "1") (pinfunction "1_1") (pintype "passive"))
      (node (ref "REG5") (pin "2") (pinfunction "GND_2") (pintype "power_in"))
      (node (ref "S5") (pin "B") (pinfunction "B_B") (pintype "passive"))
      (node (ref "S5") (pin "B1") (pinfunction "B1_B1") (pintype "passive"))
      (node (ref "U10") (pin "4") (pinfunction "V-_4") (pintype "power_in"))
      (node (ref "U2") (pin "11") (pinfunction "V-_11") (pintype "power_in"))
      (node (ref "U4") (pin "4") (pinfunction "V-_4") (pintype "power_in"))
      (node (ref "U4") (pin "5") (pinfunction "+IN_5") (pintype "input"))
      (node (ref "U9") (pin "15") (pinfunction "GND_15") (pintype "power_in"))
    )
    (net (code "6") (name "Net-(C20-Pad1)") (class "Default")
      (node (ref "C20") (pin "1") (pinfunction "1_1") (pintype "passive"))
      (node (ref "R7") (pin "2") (pinfunction "2_2") (pintype "passive"))
      (node (ref "R8") (pin "1") (pinfunction "1_1") (pintype "passive"))
    )
    (net (code "7") (name "Net-(C21-Pad1)") (class "Default")
      (node (ref "C21") (pin "1") (pinfunction "1_1") (pintype "passive"))
      (node (ref "J4") (pin "2") (pinfunction "2_2") (pintype "passive"))
      (node (ref "J4") (pin "5") (pinfunction "5_5") (pintype "passive"))
      (node (ref "R7") (pin "1") (pinfunction "1_1") (pintype "passive"))
    )
    (net (code "8") (name "Net-(C22-Pad2)") (class "Default")
      (node (ref "C22") (pin "2") (pinfunction "2_2") (pintype "passive"))
      (node (ref "R13") (pin "2") (pinfunction "2_2") (pintype "passive"))
    )
    (net (code "9") (name "Net-(C23-Pad1)") (class "Default")
      (node (ref "C23") (pin "1") (pinfunction "1_1") (pintype "passive"))
      (node (ref "R14") (pin "2") (pinfunction "2_2") (pintype "passive"))
    )
    (net (code "10") (name "Net-(C24-Pad1)") (class "Default")
      (node (ref "C24") (pin "1") (pinfunction "1_1") (pintype "passive"))
      (node (ref "R15") (pin "2") (pinfunction "2_2") (pintype "passive"))
    )
    (net (code "11") (name "Net-(C43-Pad1)") (class "Default")
      (node (ref "C43") (pin "1") (pinfunction "1_1") (pintype "passive"))
      (node (ref "R11") (pin "1") (pinfunction "1_1") (pintype "passive"))
    )
    (net (code "12") (name "Net-(DAC-VOUT_A)") (class "Default")
      (node (ref "DAC") (pin "8") (pinfunction "VOUT_A_8") (pintype "output"))
      (node (ref "R42") (pin "1") (pinfunction "1_1") (pintype "passive"))
    )
    (net (code "13") (name "Net-(DAC-VOUT_B)") (class "Default")
      (node (ref "DAC") (pin "5") (pinfunction "VOUT_B_5") (pintype "output"))
      (node (ref "R31") (pin "1") (pinfunction "1_1") (pintype "passive"))
    )
    (net (code "14") (name "Net-(IC1-(ADC2)PA2)") (class "Default")
      (node (ref "D5") (pin "C") (pinfunction "C_C") (pintype "passive"))
      (node (ref "IC1") (pin "35") (pinfunction "(ADC2)PA2_35") (pintype "bidirectional"))
      (node (ref "R3") (pin "1") (pinfunction "1_1") (pintype "passive"))
      (node (ref "R4") (pin "2") (pinfunction "2_2") (pintype "passive"))
    )
    (net (code "15") (name "Net-(IC1-(ADC3)PA3)") (class "Default")
      (node (ref "IC1") (pin "34") (pinfunction "(ADC3)PA3_34") (pintype "bidirectional"))
      (node (ref "R5") (pin "1") (pinfunction "1_1") (pintype "passive"))
      (node (ref "R6") (pin "2") (pinfunction "2_2") (pintype "passive"))
    )
    (net (code "16") (name "Net-(IC1-XTAL1)") (class "Default")
      (node (ref "C15") (pin "1") (pinfunction "1_1") (pintype "passive"))
      (node (ref "IC1") (pin "8") (pinfunction "XTAL1_8") (pintype "bidirectional"))
      (node (ref "Y2") (pin "1") (pinfunction "1_1") (pintype "passive"))
    )
    (net (code "17") (name "Net-(IC1-XTAL2)") (class "Default")
      (node (ref "C16") (pin "1") (pinfunction "1_1") (pintype "passive"))
      (node (ref "IC1") (pin "7") (pinfunction "XTAL2_7") (pintype "bidirectional"))
      (node (ref "Y2") (pin "2") (pinfunction "2_2") (pintype "passive"))
    )
    (net (code "18") (name "Net-(J2-Pad2)") (class "Default")
      (node (ref "J2") (pin "2") (pinfunction "2_2") (pintype "passive"))
      (node (ref "R18") (pin "1") (pinfunction "1_1") (pintype "passive"))
      (node (ref "R19") (pin "2") (pinfunction "2_2") (pintype "passive"))
    )
    (net (code "19") (name "Net-(J2-Pad5)") (class "Default")
      (node (ref "J2") (pin "5") (pinfunction "5_5") (pintype "passive"))
      (node (ref "R62") (pin "1") (pinfunction "1_1") (pintype "passive"))
    )
    (net (code "20") (name "Net-(J5-Pad2)") (class "Default")
      (node (ref "J5") (pin "2") (pinfunction "2_2") (pintype "passive"))
      (node (ref "R15") (pin "1") (pinfunction "1_1") (pintype "passive"))
    )
    (net (code "21") (name "Net-(J5-Pad5)") (class "Default")
      (node (ref "J5") (pin "5") (pinfunction "5_5") (pintype "passive"))
      (node (ref "R14") (pin "1") (pinfunction "1_1") (pintype "passive"))
    )
    (net (code "22") (name "Net-(J6-Pad1)") (class "Default")
      (node (ref "J6") (pin "1") (pinfunction "1_1") (pintype "passive"))
      (node (ref "TR1") (pin "1") (pinfunction "1_1") (pintype "passive"))
    )
    (net (code "23") (name "Net-(J6-Pad5)") (class "Default")
      (node (ref "J6") (pin "5") (pinfunction "5_5") (pintype "passive"))
      (node (ref "TR1") (pin "3") (pinfunction "3_3") (pintype "passive"))
    )
    (net (code "24") (name "Net-(J7-Pad1)") (class "Default")
      (node (ref "J7") (pin "1") (pinfunction "1_1") (pintype "passive"))
      (node (ref "TR2") (pin "1") (pinfunction "1_1") (pintype "passive"))
    )
    (net (code "25") (name "Net-(J7-Pad5)") (class "Default")
      (node (ref "J7") (pin "5") (pinfunction "5_5") (pintype "passive"))
      (node (ref "TR2") (pin "3") (pinfunction "3_3") (pintype "passive"))
    )
    (net (code "26") (name "Net-(J9-Pad2)") (class "Default")
      (node (ref "J9") (pin "2") (pinfunction "2_2") (pintype "passive"))
      (node (ref "R58") (pin "2") (pinfunction "2_2") (pintype "passive"))
      (node (ref "R9") (pin "1") (pinfunction "1_1") (pintype "passive"))
    )
    (net (code "27") (name "Net-(Q1-D-Pad2)") (class "Default")
      (node (ref "Q1") (pin "2") (pinfunction "D_2") (pintype "passive"))
      (node (ref "Q1") (pin "4") (pinfunction "D_4") (pintype "passive"))
      (node (ref "TR1") (pin "4") (pinfunction "4_4") (pintype "passive"))
    )
    (net (code "28") (name "Net-(Q1-G)") (class "Default")
      (node (ref "Q1") (pin "1") (pinfunction "G_1") (pintype "passive"))
      (node (ref "R38") (pin "2") (pinfunction "2_2") (pintype "passive"))
    )
    (net (code "29") (name "Net-(Q2-D-Pad2)") (class "Default")
      (node (ref "Q2") (pin "2") (pinfunction "D_2") (pintype "passive"))
      (node (ref "Q2") (pin "4") (pinfunction "D_4") (pintype "passive"))
      (node (ref "TR1") (pin "6") (pinfunction "6_6") (pintype "passive"))
    )
    (net (code "30") (name "Net-(Q2-G)") (class "Default")
      (node (ref "Q2") (pin "1") (pinfunction "G_1") (pintype "passive"))
      (node (ref "R41") (pin "2") (pinfunction "2_2") (pintype "passive"))
    )
    (net (code "31") (name "Net-(Q3-D-Pad2)") (class "Default")
      (node (ref "Q3") (pin "2") (pinfunction "D_2") (pintype "passive"))
      (node (ref "Q3") (pin "4") (pinfunction "D_4") (pintype "passive"))
      (node (ref "TR1") (pin "5") (pinfunction "5_5") (pintype "passive"))
    )
    (net (code "32") (name "Net-(Q3-G)") (class "Default")
      (node (ref "C39") (pin "1") (pinfunction "1_1") (pintype "passive"))
      (node (ref "Q3") (pin "1") (pinfunction "G_1") (pintype "passive"))
      (node (ref "R39") (pin "2") (pinfunction "2_2") (pintype "passive"))
    )
    (net (code "33") (name "Net-(Q4-D-Pad2)") (class "Default")
      (node (ref "Q4") (pin "2") (pinfunction "D_2") (pintype "passive"))
      (node (ref "Q4") (pin "4") (pinfunction "D_4") (pintype "passive"))
      (node (ref "TR2") (pin "4") (pinfunction "4_4") (pintype "passive"))
    )
    (net (code "34") (name "Net-(Q4-G)") (class "Default")
      (node (ref "Q4") (pin "1") (pinfunction "G_1") (pintype "passive"))
      (node (ref "R49") (pin "2") (pinfunction "2_2") (pintype "passive"))
    )
    (net (code "35") (name "Net-(Q5-D-Pad2)") (class "Default")
      (node (ref "Q5") (pin "2") (pinfunction "D_2") (pintype "passive"))
      (node (ref "Q5") (pin "4") (pinfunction "D_4") (pintype "passive"))
      (node (ref "TR2") (pin "6") (pinfunction "6_6") (pintype "passive"))
    )
    (net (code "36") (name "Net-(Q5-G)") (class "Default")
      (node (ref "Q5") (pin "1") (pinfunction "G_1") (pintype "passive"))
      (node (ref "R52") (pin "2") (pinfunction "2_2") (pintype "passive"))
    )
    (net (code "37") (name "Net-(Q6-D-Pad2)") (class "Default")
      (node (ref "Q6") (pin "2") (pinfunction "D_2") (pintype "passive"))
      (node (ref "Q6") (pin "4") (pinfunction "D_4") (pintype "passive"))
      (node (ref "TR2") (pin "5") (pinfunction "5_5") (pintype "passive"))
    )
    (net (code "38") (name "Net-(Q6-G)") (class "Default")
      (node (ref "C40") (pin "1") (pinfunction "1_1") (pintype "passive"))
      (node (ref "Q6") (pin "1") (pinfunction "G_1") (pintype "passive"))
      (node (ref "R50") (pin "2") (pinfunction "2_2") (pintype "passive"))
    )
    (net (code "39") (name "Net-(R55-Pad2)") (class "Default")
      (node (ref "R55") (pin "2") (pinfunction "2_2") (pintype "passive"))
      (node (ref "TU") (pin "1") (pinfunction "1_1") (pintype "passive"))
    )
    (net (code "40") (name "Net-(S5-P)") (class "Default")
      (node (ref "D4") (pin "C") (pinfunction "C_C") (pintype "passive"))
      (node (ref "F1") (pin "2") (pinfunction "2_2") (pintype "passive"))
      (node (ref "S5") (pin "2") (pinfunction "P_2") (pintype "passive"))
      (node (ref "S5") (pin "3") (pinfunction "S_3") (pintype "passive"))
    )
    (net (code "41") (name "Net-(U2A-+IN)") (class "Default")
      (node (ref "C28") (pin "2") (pinfunction "2_2") (pintype "passive"))
      (node (ref "R21") (pin "2") (pinfunction "2_2") (pintype "passive"))
      (node (ref "R62") (pin "2") (pinfunction "2_2") (pintype "passive"))
      (node (ref "U2") (pin "3") (pinfunction "+IN_3") (pintype "input"))
    )
    (net (code "42") (name "Net-(U2A--IN)") (class "Default")
      (node (ref "R24") (pin "1") (pinfunction "1_1") (pintype "passive"))
      (node (ref "R25") (pin "1") (pinfunction "1_1") (pintype "passive"))
      (node (ref "U2") (pin "2") (pinfunction "-IN_2") (pintype "input"))
    )
    (net (code "43") (name "Net-(U2A-OUT)") (class "Default")
      (node (ref "D2") (pin "A") (pinfunction "A_A") (pintype "passive"))
      (node (ref "R25") (pin "2") (pinfunction "2_2") (pintype "passive"))
      (node (ref "U2") (pin "1") (pinfunction "OUT_1") (pintype "output"))
      (node (ref "U2") (pin "12") (pinfunction "+IN_12") (pintype "input"))
    )
    (net (code "44") (name "Net-(U2B-+IN)") (class "Default")
      (node (ref "C26") (pin "2") (pinfunction "2_2") (pintype "passive"))
      (node (ref "R20") (pin "2") (pinfunction "2_2") (pintype "passive"))
      (node (ref "U2") (pin "5") (pinfunction "+IN_5") (pintype "input"))
    )
    (net (code "45") (name "Net-(U2B--IN)") (class "Default")
      (node (ref "R22") (pin "2") (pinfunction "2_2") (pintype "passive"))
      (node (ref "R23") (pin "1") (pinfunction "1_1") (pintype "passive"))
      (node (ref "U2") (pin "6") (pinfunction "-IN_6") (pintype "input"))
    )
    (net (code "46") (name "Net-(U2B-OUT)") (class "Default")
      (node (ref "D3") (pin "A") (pinfunction "A_A") (pintype "passive"))
      (node (ref "R23") (pin "2") (pinfunction "2_2") (pintype "passive"))
      (node (ref "U2") (pin "10") (pinfunction "+IN_10") (pintype "input"))
      (node (ref "U2") (pin "7") (pinfunction "OUT_7") (pintype "output"))
    )
    (net (code "47") (name "Net-(U2C--IN)") (class "Default")
      (node (ref "R26") (pin "1") (pinfunction "1_1") (pintype "passive"))
      (node (ref "R27") (pin "1") (pinfunction "1_1") (pintype "passive"))
      (node (ref "U2") (pin "13") (pinfunction "-IN_13") (pintype "input"))
      (node (ref "U2") (pin "9") (pinfunction "-IN_9") (pintype "input"))
    )
    (net (code "48") (name "Net-(U4A-+IN)") (class "Default")
      (node (ref "C21") (pin "2") (pinfunction "2_2") (pintype "passive"))
      (node (ref "R10") (pin "2") (pinfunction "2_2") (pintype "passive"))
      (node (ref "R61") (pin "1") (pinfunction "1_1") (pintype "passive"))
      (node (ref "U4") (pin "3") (pinfunction "+IN_3") (pintype "input"))
    )
    (net (code "49") (name "Net-(U4A--IN)") (class "Default")
      (node (ref "R11") (pin "2") (pinfunction "2_2") (pintype "passive"))
      (node (ref "R12") (pin "1") (pinfunction "1_1") (pintype "passive"))
      (node (ref "U4") (pin "2") (pinfunction "-IN_2") (pintype "input"))
    )
    (net (code "50") (name "Net-(U4A-OUT)") (class "Default")
      (node (ref "R12") (pin "2") (pinfunction "2_2") (pintype "passive"))
      (node (ref "R13") (pin "1") (pinfunction "1_1") (pintype "passive"))
      (node (ref "U4") (pin "1") (pinfunction "OUT_1") (pintype "output"))
      (node (ref "U4") (pin "6") (pinfunction "-IN_6") (pintype "input"))
    )
    (net (code "51") (name "Net-(U9A-C1+)") (class "Default")
      (node (ref "C35") (pin "1") (pinfunction "1_1") (pintype "passive"))
      (node (ref "U9") (pin "1") (pinfunction "C1+_1") (pintype "bidirectional"))
    )
    (net (code "52") (name "Net-(U9A-C1-)") (class "Default")
      (node (ref "C35") (pin "2") (pinfunction "2_2") (pintype "passive"))
      (node (ref "U9") (pin "3") (pinfunction "C1-_3") (pintype "bidirectional"))
    )
    (net (code "53") (name "Net-(U9A-C2+)") (class "Default")
      (node (ref "C36") (pin "1") (pinfunction "1_1") (pintype "passive"))
      (node (ref "U9") (pin "4") (pinfunction "C2+_4") (pintype "bidirectional"))
    )
    (net (code "54") (name "Net-(U9A-C2-)") (class "Default")
      (node (ref "C36") (pin "2") (pinfunction "2_2") (pintype "passive"))
      (node (ref "U9") (pin "5") (pinfunction "C2-_5") (pintype "bidirectional"))
    )
    (net (code "55") (name "Net-(U9A-R1IN)") (class "Default")
      (node (ref "J3") (pin "2") (pinfunction "2_2") (pintype "passive"))
      (node (ref "U9") (pin "13") (pinfunction "R1IN_13") (pintype "input"))
    )
    (net (code "56") (name "Net-(U9A-R2IN)") (class "Default")
      (node (ref "J3") (pin "4") (pinfunction "4_4") (pintype "passive"))
      (node (ref "U9") (pin "8") (pinfunction "R2IN_8") (pintype "input"))
    )
    (net (code "57") (name "Net-(U9A-R2OUT)") (class "Default")
      (node (ref "R9") (pin "2") (pinfunction "2_2") (pintype "passive"))
      (node (ref "U9") (pin "9") (pinfunction "R2OUT_9") (pintype "output"))
    )
    (net (code "58") (name "Net-(U9A-T1OUT)") (class "Default")
      (node (ref "J3") (pin "5") (pinfunction "5_5") (pintype "passive"))
      (node (ref "U9") (pin "14") (pinfunction "T1OUT_14") (pintype "output"))
    )
    (net (code "59") (name "Net-(U9A-T2IN)") (class "Default")
      (node (ref "J9") (pin "3") (pinfunction "3_3") (pintype "passive"))
      (node (ref "U9") (pin "10") (pinfunction "T2IN_10") (pintype "input"))
    )
    (net (code "60") (name "Net-(U9A-T2OUT)") (class "Default")
      (node (ref "J3") (pin "3") (pinfunction "3_3") (pintype "passive"))
      (node (ref "U9") (pin "7") (pinfunction "T2OUT_7") (pintype "output"))
    )
    (net (code "61") (name "Net-(U9A-V+)") (class "Default")
      (node (ref "C33") (pin "2") (pinfunction "2_2") (pintype "passive"))
      (node (ref "U9") (pin "2") (pinfunction "V+_2") (pintype "bidirectional"))
    )
    (net (code "62") (name "Net-(U9A-V-)") (class "Default")
      (node (ref "C34") (pin "1") (pinfunction "1_1") (pintype "passive"))
      (node (ref "U9") (pin "6") (pinfunction "V-_6") (pintype "bidirectional"))
    )
    (net (code "63") (name "Net-(U10A-+IN)") (class "Default")
      (node (ref "R31") (pin "2") (pinfunction "2_2") (pintype "passive"))
      (node (ref "R32") (pin "1") (pinfunction "1_1") (pintype "passive"))
      (node (ref "R33") (pin "2") (pinfunction "2_2") (pintype "passive"))
      (node (ref "U10") (pin "3") (pinfunction "+IN_3") (pintype "input"))
    )
    (net (code "64") (name "Net-(U10A--IN)") (class "Default")
      (node (ref "R34") (pin "1") (pinfunction "1_1") (pintype "passive"))
      (node (ref "R35") (pin "2") (pinfunction "2_2") (pintype "passive"))
      (node (ref "R36") (pin "1") (pinfunction "1_1") (pintype "passive"))
      (node (ref "U10") (pin "2") (pinfunction "-IN_2") (pintype "input"))
    )
    (net (code "65") (name "Net-(U10A-OUT)") (class "Default")
      (node (ref "R36") (pin "2") (pinfunction "2_2") (pintype "passive"))
      (node (ref "R39") (pin "1") (pinfunction "1_1") (pintype "passive"))
      (node (ref "U10") (pin "1") (pinfunction "OUT_1") (pintype "output"))
    )
    (net (code "66") (name "Net-(U10B-+IN)") (class "Default")
      (node (ref "R42") (pin "2") (pinfunction "2_2") (pintype "passive"))
      (node (ref "R43") (pin "1") (pinfunction "1_1") (pintype "passive"))
      (node (ref "R44") (pin "2") (pinfunction "2_2") (pintype "passive"))
      (node (ref "U10") (pin "5") (pinfunction "+IN_5") (pintype "input"))
    )
    (net (code "67") (name "Net-(U10B--IN)") (class "Default")
      (node (ref "R45") (pin "1") (pinfunction "1_1") (pintype "passive"))
      (node (ref "R46") (pin "2") (pinfunction "2_2") (pintype "passive"))
      (node (ref "R47") (pin "1") (pinfunction "1_1") (pintype "passive"))
      (node (ref "U10") (pin "6") (pinfunction "-IN_6") (pintype "input"))
    )
    (net (code "68") (name "Net-(U10B-OUT)") (class "Default")
      (node (ref "R47") (pin "2") (pinfunction "2_2") (pintype "passive"))
      (node (ref "R50") (pin "1") (pinfunction "1_1") (pintype "passive"))
      (node (ref "U10") (pin "7") (pinfunction "OUT_7") (pintype "output"))
    )
    (net (code "69") (name "PA0") (class "Default")
      (node (ref "IC1") (pin "37") (pinfunction "(ADC0)PA0_37") (pintype "bidirectional"))
      (node (ref "Q1") (pin "3") (pinfunction "S_3") (pintype "passive"))
      (node (ref "Q2") (pin "3") (pinfunction "S_3") (pintype "passive"))
      (node (ref "Q4") (pin "3") (pinfunction "S_3") (pintype "passive"))
      (node (ref "Q5") (pin "3") (pinfunction "S_3") (pintype "passive"))
      (node (ref "R30") (pin "2") (pinfunction "2_2") (pintype "passive"))
      (node (ref "R54") (pin "2") (pinfunction "2_2") (pintype "passive"))
      (node (ref "TU") (pin "2") (pinfunction "2_2") (pintype "passive"))
    )
    (net (code "70") (name "PA1") (class "Default")
      (node (ref "C25") (pin "1") (pinfunction "1_1") (pintype "passive"))
      (node (ref "C26") (pin "1") (pinfunction "1_1") (pintype "passive"))
      (node (ref "IC1") (pin "36") (pinfunction "(ADC1)PA1_36") (pintype "bidirectional"))
      (node (ref "J11") (pin "5") (pinfunction "KL_5") (pintype "passive"))
    )
    (net (code "71") (name "PA4") (class "Default")
      (node (ref "IC1") (pin "33") (pinfunction "(ADC4)PA4_33") (pintype "bidirectional"))
      (node (ref "J11") (pin "9") (pinfunction "KL_9") (pintype "passive"))
    )
    (net (code "72") (name "PA5") (class "Default")
      (node (ref "IC1") (pin "32") (pinfunction "(ADC5)PA5_32") (pintype "bidirectional"))
      (node (ref "J11") (pin "11") (pinfunction "KL_11") (pintype "passive"))
    )
    (net (code "73") (name "PA6") (class "Default")
      (node (ref "C31") (pin "1") (pinfunction "1_1") (pintype "passive"))
      (node (ref "D2") (pin "C") (pinfunction "C_C") (pintype "passive"))
      (node (ref "IC1") (pin "31") (pinfunction "(ADC6)PA6_31") (pintype "bidirectional"))
      (node (ref "R29") (pin "1") (pinfunction "1_1") (pintype "passive"))
    )
    (net (code "74") (name "PA7") (class "Default")
      (node (ref "C30") (pin "1") (pinfunction "1_1") (pintype "passive"))
      (node (ref "D3") (pin "C") (pinfunction "C_C") (pintype "passive"))
      (node (ref "IC1") (pin "30") (pinfunction "(ADC7)PA7_30") (pintype "bidirectional"))
      (node (ref "R28") (pin "1") (pinfunction "1_1") (pintype "passive"))
    )
    (net (code "75") (name "PB0") (class "Default")
      (node (ref "IC1") (pin "40") (pinfunction "(T0/XCK)PB0_40") (pintype "bidirectional"))
      (node (ref "R48") (pin "2") (pinfunction "2_2") (pintype "passive"))
      (node (ref "R49") (pin "1") (pinfunction "1_1") (pintype "passive"))
    )
    (net (code "76") (name "PB1") (class "Default")
      (node (ref "IC1") (pin "41") (pinfunction "(T1)PB1_41") (pintype "bidirectional"))
      (node (ref "R51") (pin "2") (pinfunction "2_2") (pintype "passive"))
      (node (ref "R52") (pin "1") (pinfunction "1_1") (pintype "passive"))
    )
    (net (code "77") (name "PB2") (class "Default")
      (node (ref "IC1") (pin "42") (pinfunction "(AIN0/INT2)PB2_42") (pintype "bidirectional"))
      (node (ref "R37") (pin "2") (pinfunction "2_2") (pintype "passive"))
      (node (ref "R38") (pin "1") (pinfunction "1_1") (pintype "passive"))
    )
    (net (code "78") (name "PB3") (class "Default")
      (node (ref "IC1") (pin "43") (pinfunction "(AIN1/OC0)PB3_43") (pintype "bidirectional"))
      (node (ref "R40") (pin "2") (pinfunction "2_2") (pintype "passive"))
      (node (ref "R41") (pin "1") (pinfunction "1_1") (pintype "passive"))
    )
    (net (code "79") (name "PB5") (class "Default")
      (node (ref "DAC") (pin "3") (pinfunction "D_IN_3") (pintype "input"))
      (node (ref "IC1") (pin "1") (pinfunction "(MOSI)PB5_1") (pintype "bidirectional"))
      (node (ref "JP1") (pin "4") (pinfunction "S_4") (pintype "passive"))
    )
    (net (code "80") (name "PB6") (class "Default")
      (node (ref "IC1") (pin "2") (pinfunction "(MISO)PB6_2") (pintype "bidirectional"))
      (node (ref "JP1") (pin "1") (pinfunction "S_1") (pintype "passive"))
    )
    (net (code "81") (name "PB7") (class "Default")
      (node (ref "DAC") (pin "2") (pinfunction "SCK_2") (pintype "input"))
      (node (ref "IC1") (pin "3") (pinfunction "(SCK)PB7_3") (pintype "bidirectional"))
      (node (ref "JP1") (pin "3") (pinfunction "S_3") (pintype "passive"))
    )
    (net (code "82") (name "PC0") (class "Default")
      (node (ref "IC1") (pin "19") (pinfunction "PC0(SCL)_19") (pintype "bidirectional"))
      (node (ref "J11") (pin "2") (pinfunction "KL_2") (pintype "passive"))
    )
    (net (code "83") (name "PC1") (class "Default")
      (node (ref "IC1") (pin "20") (pinfunction "PC1(SDA)_20") (pintype "bidirectional"))
      (node (ref "J11") (pin "4") (pinfunction "KL_4") (pintype "passive"))
    )
    (net (code "84") (name "PC2") (class "Default")
      (node (ref "IC1") (pin "21") (pinfunction "(TCK)PC2_21") (pintype "bidirectional"))
      (node (ref "J11") (pin "6") (pinfunction "KL_6") (pintype "passive"))
    )
    (net (code "85") (name "PC3") (class "Default")
      (node (ref "IC1") (pin "22") (pinfunction "(TMS)PC3_22") (pintype "bidirectional"))
      (node (ref "J11") (pin "8") (pinfunction "KL_8") (pintype "passive"))
    )
    (net (code "86") (name "PC4") (class "Default")
      (node (ref "IC1") (pin "23") (pinfunction "(TDO)PC4_23") (pintype "bidirectional"))
      (node (ref "J11") (pin "10") (pinfunction "KL_10") (pintype "passive"))
    )
    (net (code "87") (name "PC5") (class "Default")
      (node (ref "IC1") (pin "24") (pinfunction "(TDI)PC5_24") (pintype "bidirectional"))
      (node (ref "J11") (pin "12") (pinfunction "KL_12") (pintype "passive"))
    )
    (net (code "88") (name "PC6") (class "Default")
      (node (ref "IC1") (pin "25") (pinfunction "(TOSC1)PC6_25") (pintype "bidirectional"))
      (node (ref "J11") (pin "14") (pinfunction "KL_14") (pintype "passive"))
    )
    (net (code "89") (name "PC7") (class "Default")
      (node (ref "IC1") (pin "26") (pinfunction "(TOSC2)PC7_26") (pintype "bidirectional"))
      (node (ref "J11") (pin "16") (pinfunction "KL_16") (pintype "passive"))
    )
    (net (code "90") (name "PD0") (class "Default")
      (node (ref "IC1") (pin "9") (pinfunction "(RXD)PD0_9") (pintype "bidirectional"))
      (node (ref "U9") (pin "12") (pinfunction "R1OUT_12") (pintype "output"))
    )
    (net (code "91") (name "PD1") (class "Default")
      (node (ref "IC1") (pin "10") (pinfunction "(TXD)PD1_10") (pintype "bidirectional"))
      (node (ref "U9") (pin "11") (pinfunction "T1IN_11") (pintype "input"))
    )
    (net (code "92") (name "PD2") (class "Default")
      (node (ref "IC1") (pin "11") (pinfunction "(INT0)PD2_11") (pintype "bidirectional"))
      (node (ref "U2") (pin "14") (pinfunction "OUT_14") (pintype "output"))
    )
    (net (code "93") (name "PD3") (class "Default")
      (node (ref "IC1") (pin "12") (pinfunction "(INT1)PD3_12") (pintype "bidirectional"))
      (node (ref "U2") (pin "8") (pinfunction "OUT_8") (pintype "output"))
    )
    (net (code "94") (name "PD5") (class "Default")
      (node (ref "IC1") (pin "14") (pinfunction "(OC1A)PD5_14") (pintype "bidirectional"))
      (node (ref "J11") (pin "15") (pinfunction "KL_15") (pintype "passive"))
    )
    (net (code "95") (name "PD6") (class "Default")
      (node (ref "IC1") (pin "15") (pinfunction "(ICP)PD6_15") (pintype "bidirectional"))
      (node (ref "J11") (pin "13") (pinfunction "KL_13") (pintype "passive"))
    )
    (net (code "96") (name "PD7") (class "Default")
      (node (ref "IC1") (pin "16") (pinfunction "(OC2)PD7_16") (pintype "bidirectional"))
      (node (ref "J11") (pin "18") (pinfunction "KL_18") (pintype "passive"))
    )
    (net (code "97") (name "RB4") (class "Default")
      (node (ref "C27") (pin "1") (pinfunction "1_1") (pintype "passive"))
      (node (ref "C28") (pin "1") (pinfunction "1_1") (pintype "passive"))
      (node (ref "J11") (pin "7") (pinfunction "KL_7") (pintype "passive"))
    )
    (net (code "98") (name "RB9") (class "Default")
      (node (ref "C22") (pin "1") (pinfunction "1_1") (pintype "passive"))
      (node (ref "C24") (pin "2") (pinfunction "2_2") (pintype "passive"))
      (node (ref "J11") (pin "3") (pinfunction "KL_3") (pintype "passive"))
      (node (ref "R17") (pin "1") (pinfunction "1_1") (pintype "passive"))
    )
    (net (code "99") (name "RB10") (class "Default")
      (node (ref "C23") (pin "2") (pinfunction "2_2") (pintype "passive"))
      (node (ref "J11") (pin "1") (pinfunction "KL_1") (pintype "passive"))
      (node (ref "R16") (pin "1") (pinfunction "1_1") (pintype "passive"))
    )
    (net (code "100") (name "RESET") (class "Default")
      (node (ref "C37") (pin "2") (pinfunction "2_2") (pintype "passive"))
      (node (ref "IC1") (pin "4") (pinfunction "RESET_4") (pintype "input"))
      (node (ref "JP1") (pin "5") (pinfunction "S_5") (pintype "passive"))
      (node (ref "R53") (pin "1") (pinfunction "1_1") (pintype "passive"))
    )
    (net (code "101") (name "STATE") (class "Default")
      (node (ref "J11") (pin "17") (pinfunction "KL_17") (pintype "passive"))
      (node (ref "J9") (pin "1") (pinfunction "1_1") (pintype "passive"))
    )
    (net (code "102") (name "V+") (class "Default")
      (node (ref "BAT") (pin "1") (pinfunction "S_1") (pintype "passive"))
      (node (ref "F1") (pin "1") (pinfunction "1_1") (pintype "passive"))
      (node (ref "J8") (pin "PWR") (pinfunction "PWR_PWR") (pintype "bidirectional"))
      (node (ref "R3") (pin "2") (pinfunction "2_2") (pintype "passive"))
    )
    (net (code "103") (name "unconnected-(IC1-(SS)PB4-Pad44)") (class "Default")
      (node (ref "IC1") (pin "44") (pinfunction "(SS)PB4_44") (pintype "bidirectional"))
    )
    (net (code "104") (name "unconnected-(J2-Pad3)") (class "Default")
      (node (ref "J2") (pin "3") (pinfunction "3_3") (pintype "passive"))
    )
    (net (code "105") (name "unconnected-(J2-Pad4)") (class "Default")
      (node (ref "J2") (pin "4") (pinfunction "4_4") (pintype "passive"))
    )
    (net (code "106") (name "unconnected-(J4-Pad3)") (class "Default")
      (node (ref "J4") (pin "3") (pinfunction "3_3") (pintype "passive"))
    )
    (net (code "107") (name "unconnected-(J4-Pad4)") (class "Default")
      (node (ref "J4") (pin "4") (pinfunction "4_4") (pintype "passive"))
    )
    (net (code "108") (name "unconnected-(J5-Pad3)") (class "Default")
      (node (ref "J5") (pin "3") (pinfunction "3_3") (pintype "passive"))
    )
    (net (code "109") (name "unconnected-(J5-Pad4)") (class "Default")
      (node (ref "J5") (pin "4") (pinfunction "4_4") (pintype "passive"))
    )
    (net (code "110") (name "unconnected-(J6-Pad2)") (class "Default")
      (node (ref "J6") (pin "2") (pinfunction "2_2") (pintype "passive"))
    )
    (net (code "111") (name "unconnected-(J6-Pad3)") (class "Default")
      (node (ref "J6") (pin "3") (pinfunction "3_3") (pintype "passive"))
    )
    (net (code "112") (name "unconnected-(J6-Pad4)") (class "Default")
      (node (ref "J6") (pin "4") (pinfunction "4_4") (pintype "passive"))
    )
    (net (code "113") (name "unconnected-(J7-Pad2)") (class "Default")
      (node (ref "J7") (pin "2") (pinfunction "2_2") (pintype "passive"))
    )
    (net (code "114") (name "unconnected-(J7-Pad3)") (class "Default")
      (node (ref "J7") (pin "3") (pinfunction "3_3") (pintype "passive"))
    )
    (net (code "115") (name "unconnected-(J7-Pad4)") (class "Default")
      (node (ref "J7") (pin "4") (pinfunction "4_4") (pintype "passive"))
    )
    (net (code "116") (name "unconnected-(J9-Pad6)") (class "Default")
      (node (ref "J9") (pin "6") (pinfunction "6_6") (pintype "passive"))
    )
    (net (code "117") (name "unconnected-(TR1-Pad2)") (class "Default")
      (node (ref "TR1") (pin "2") (pinfunction "2_2") (pintype "passive"))
    )
    (net (code "118") (name "unconnected-(TR2-Pad2)") (class "Default")
      (node (ref "TR2") (pin "2") (pinfunction "2_2") (pintype "passive"))
    )
    (net (code "119") (name "unconnected-(U4B-OUT-Pad7)") (class "Default")
      (node (ref "U4") (pin "7") (pinfunction "OUT_7") (pintype "output"))
    )
    (net (code "120") (name "~{CS}") (class "Default")
      (node (ref "DAC") (pin "1") (pinfunction "CS/LD_1") (pintype "input"))
      (node (ref "IC1") (pin "13") (pinfunction "(OC1B)PD4_13") (pintype "bidirectional"))
    )
  )
)
